# RX8E.net
KiCad netlist of a schematic drawn in EAGLE
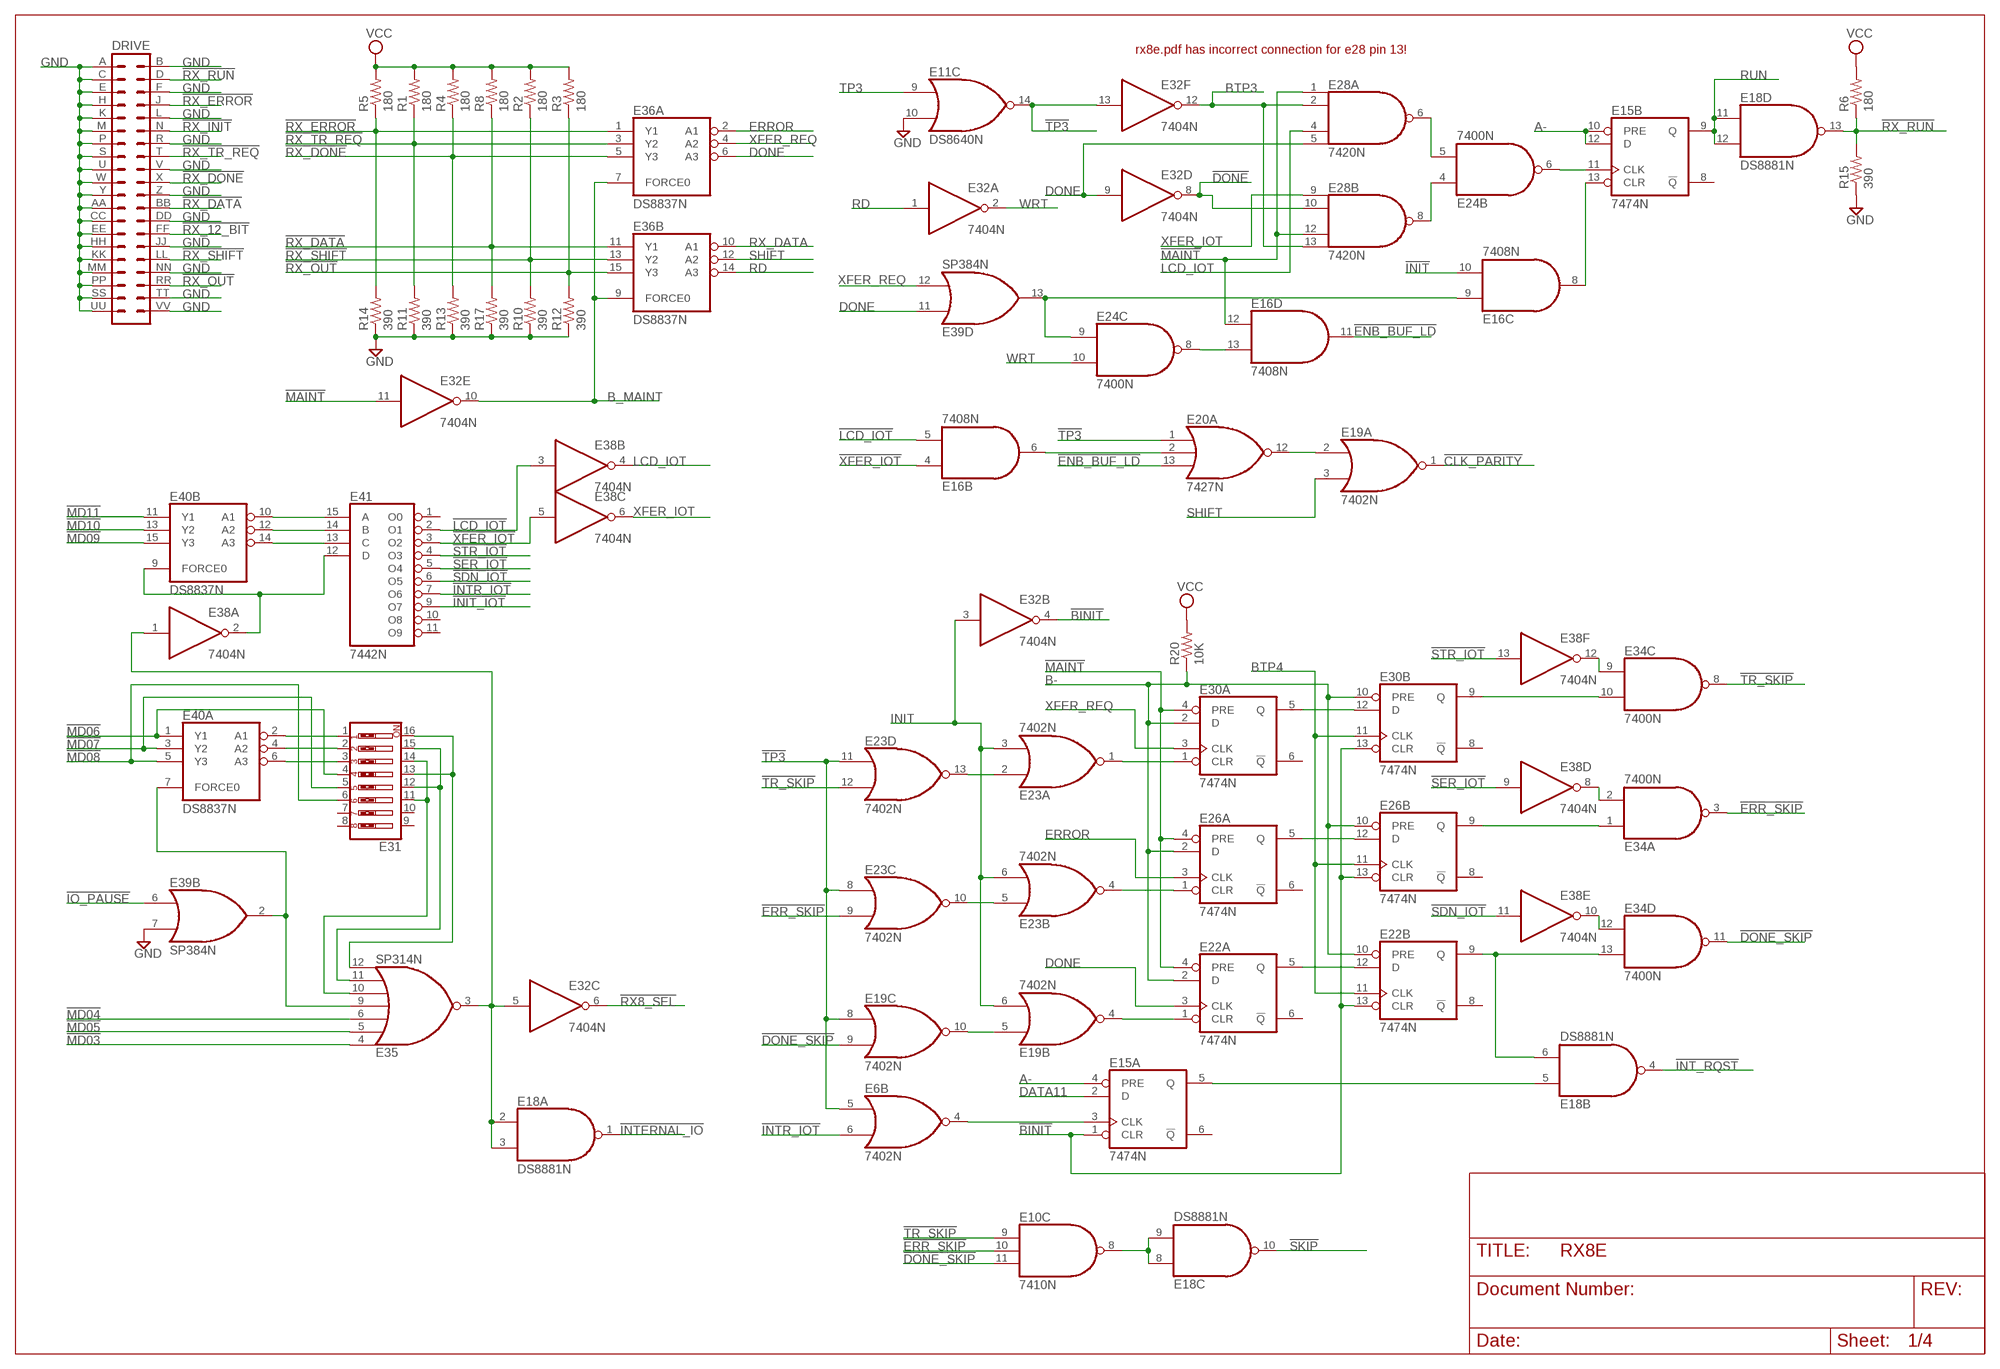
[diagram p0: schematic, sheet 1]
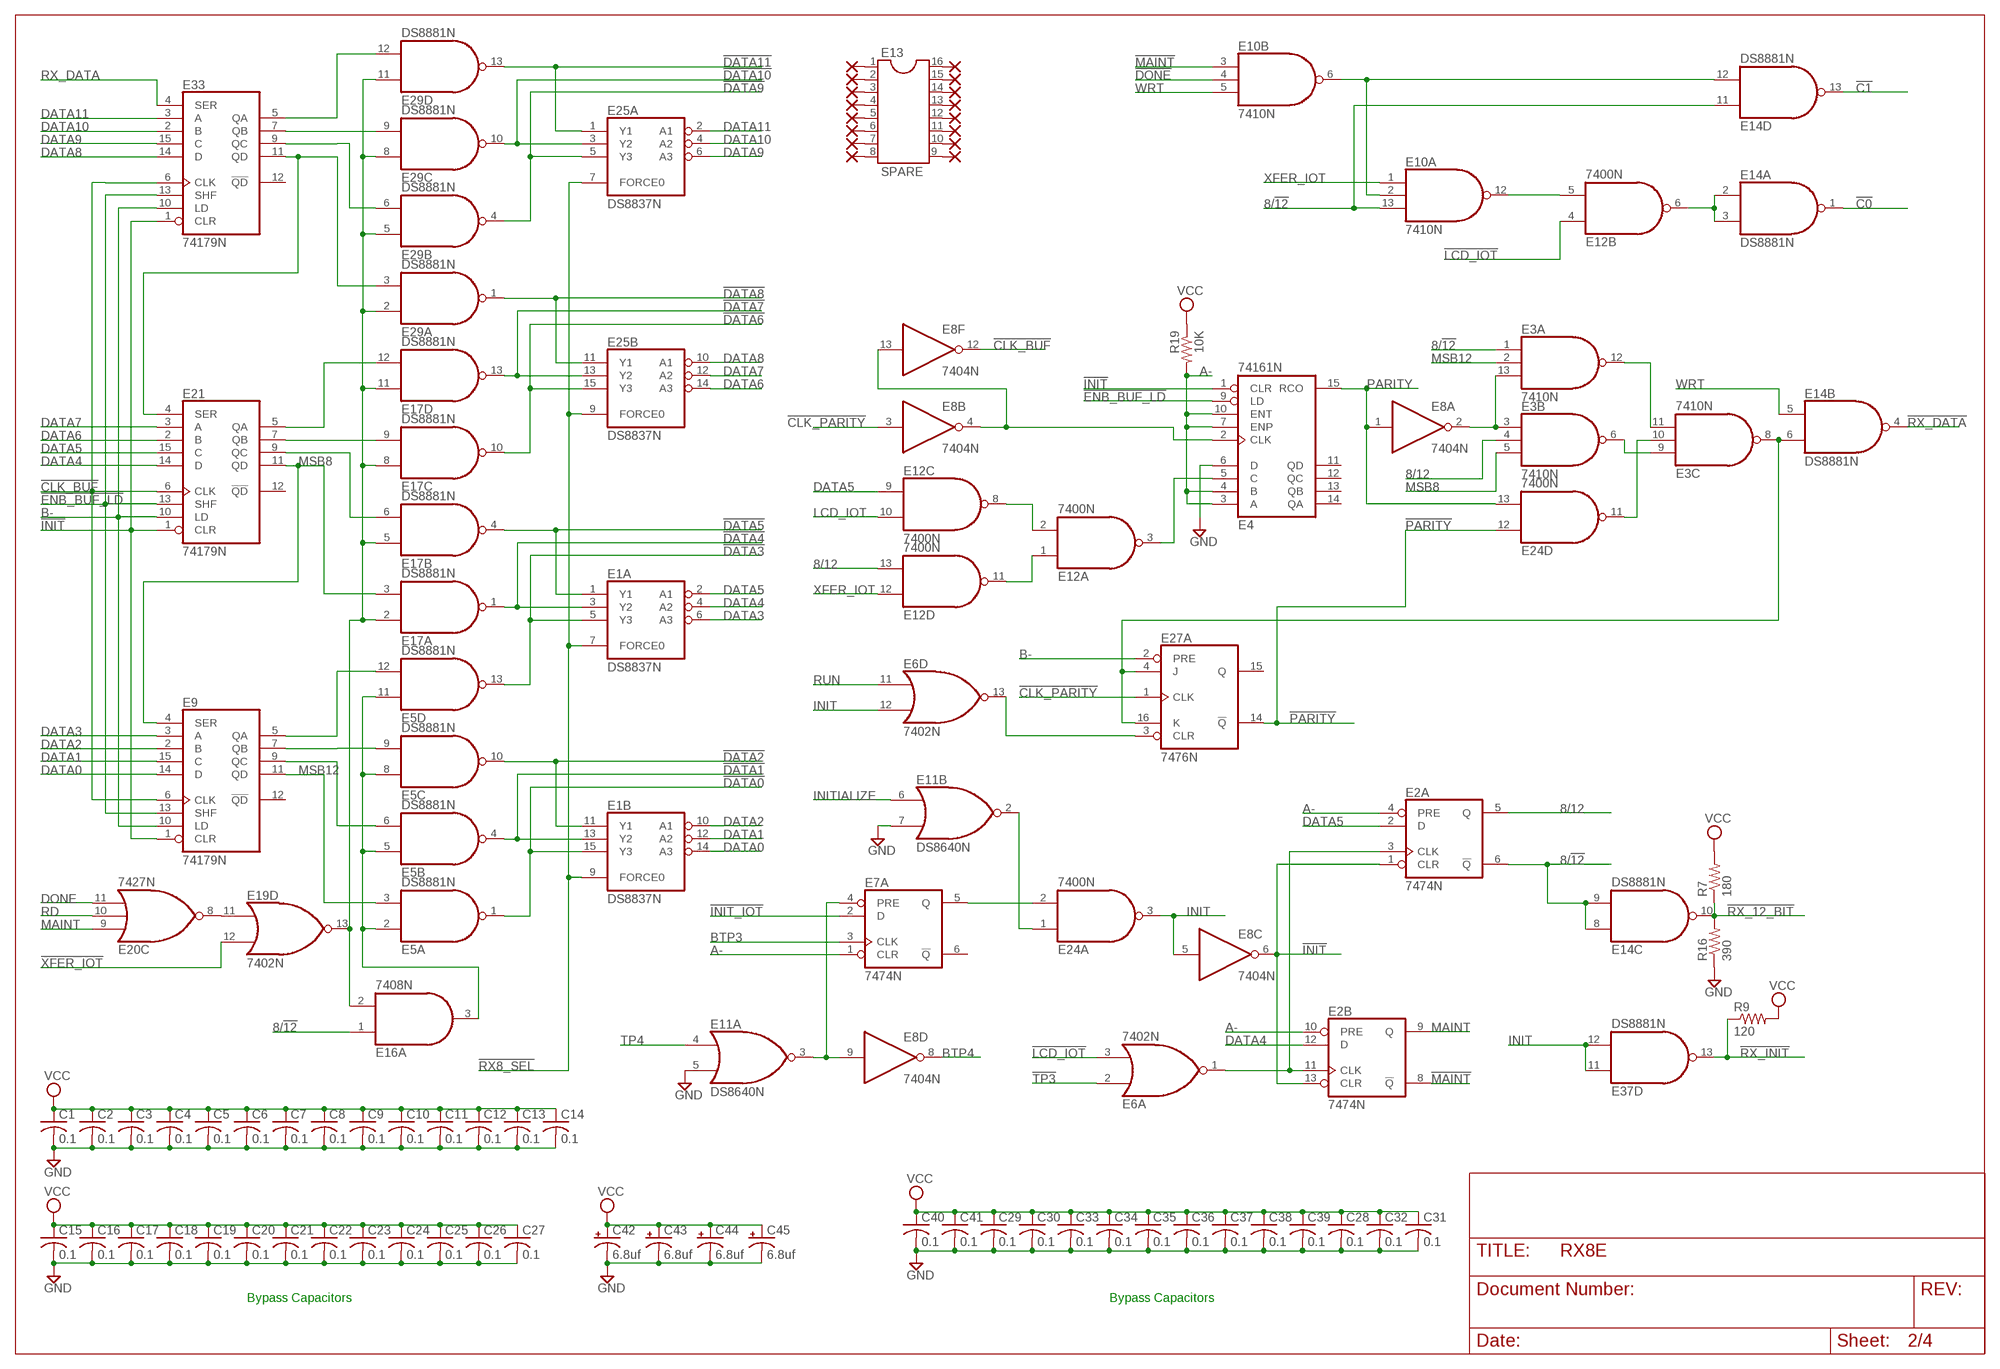
[diagram p1: schematic, sheet 2]
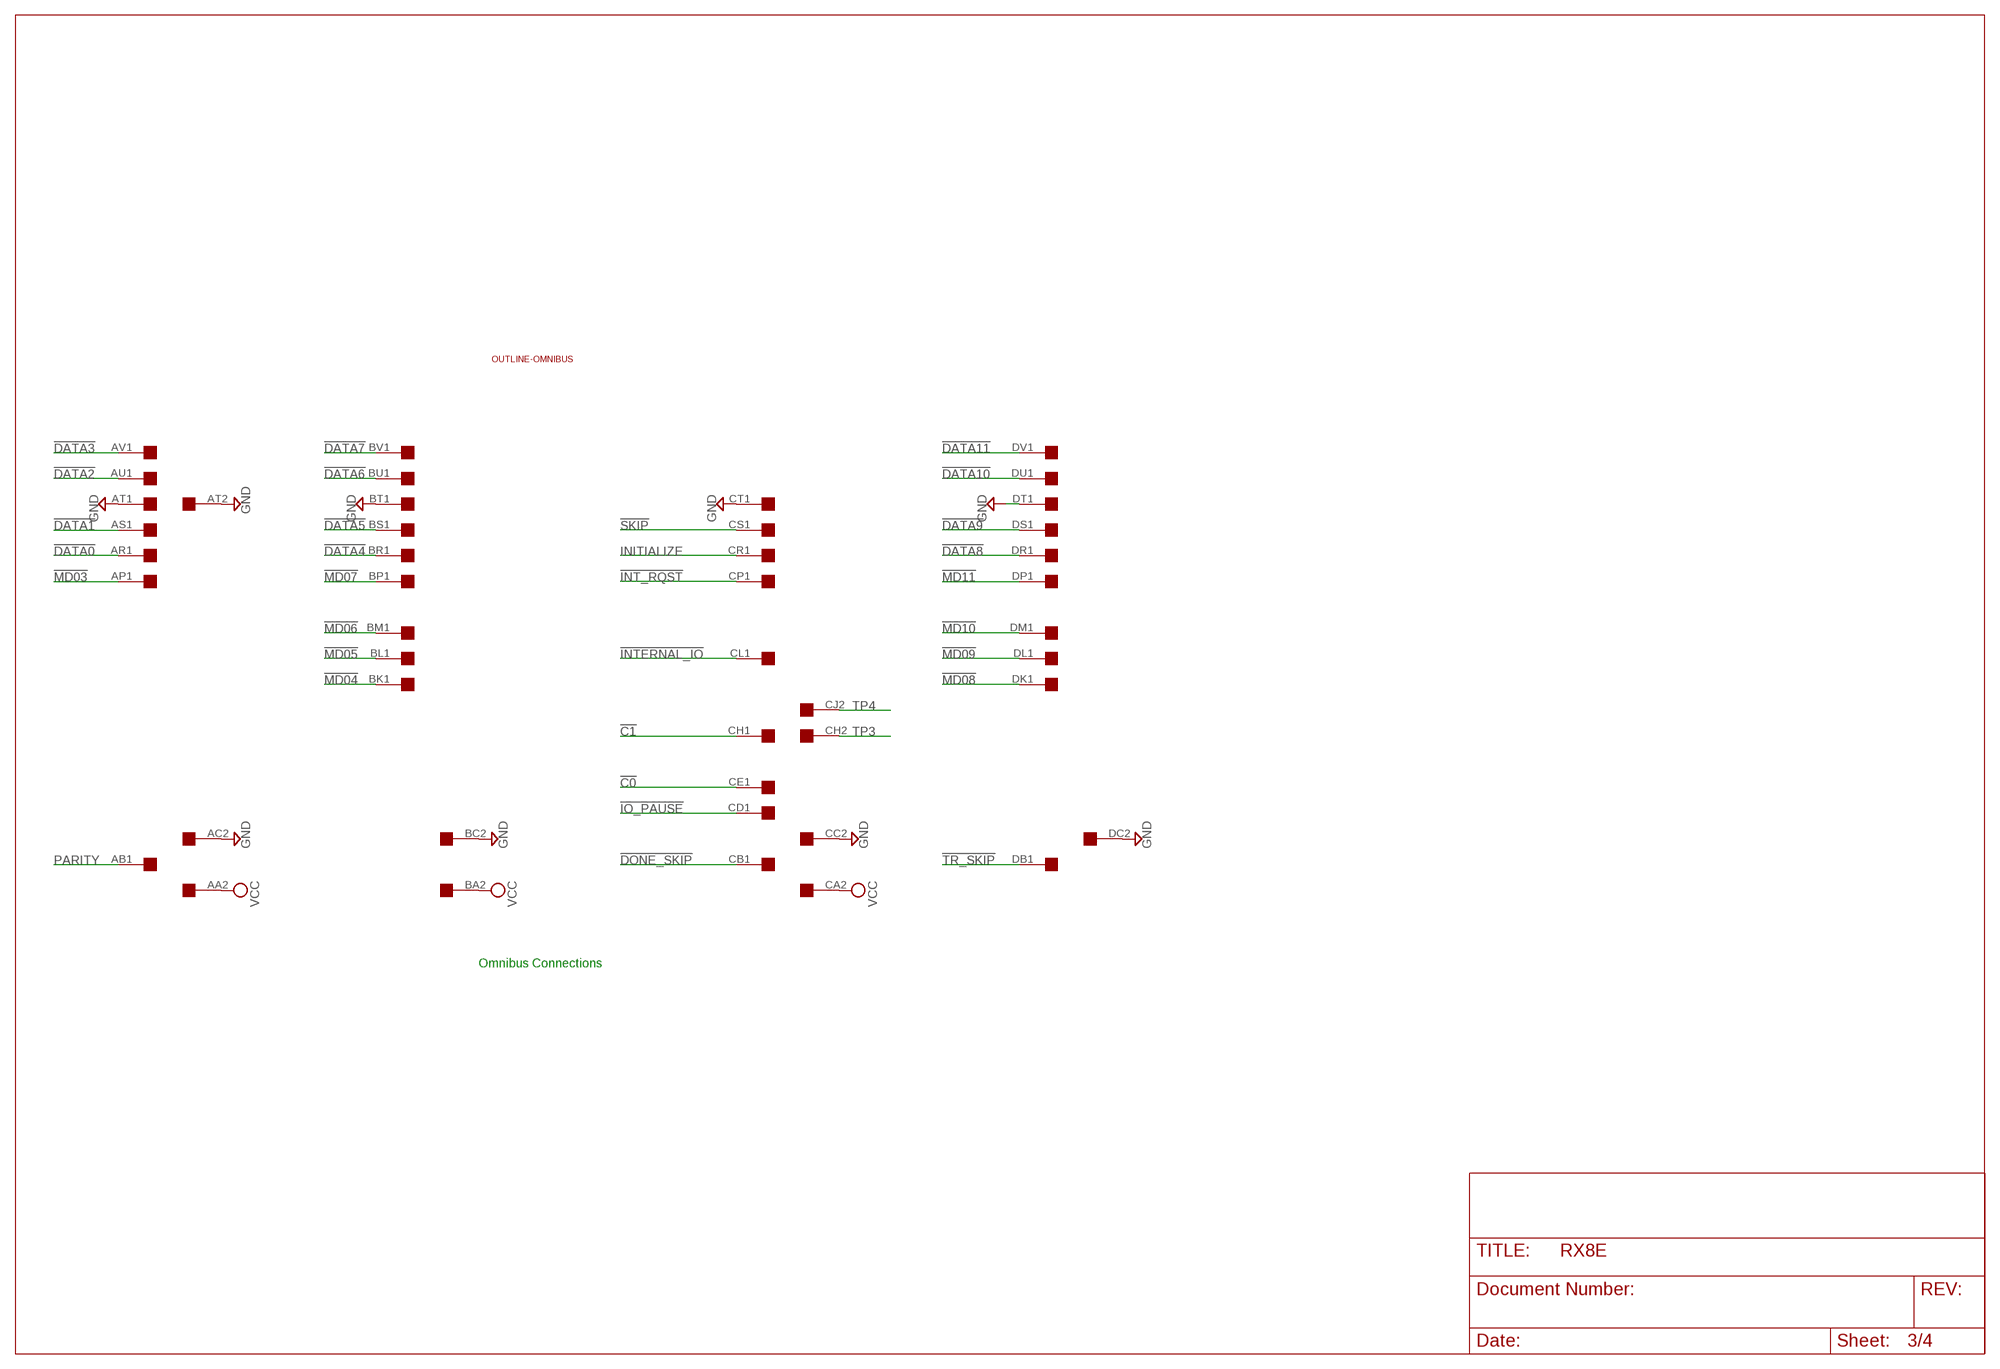
[diagram p2: schematic, sheet 3]
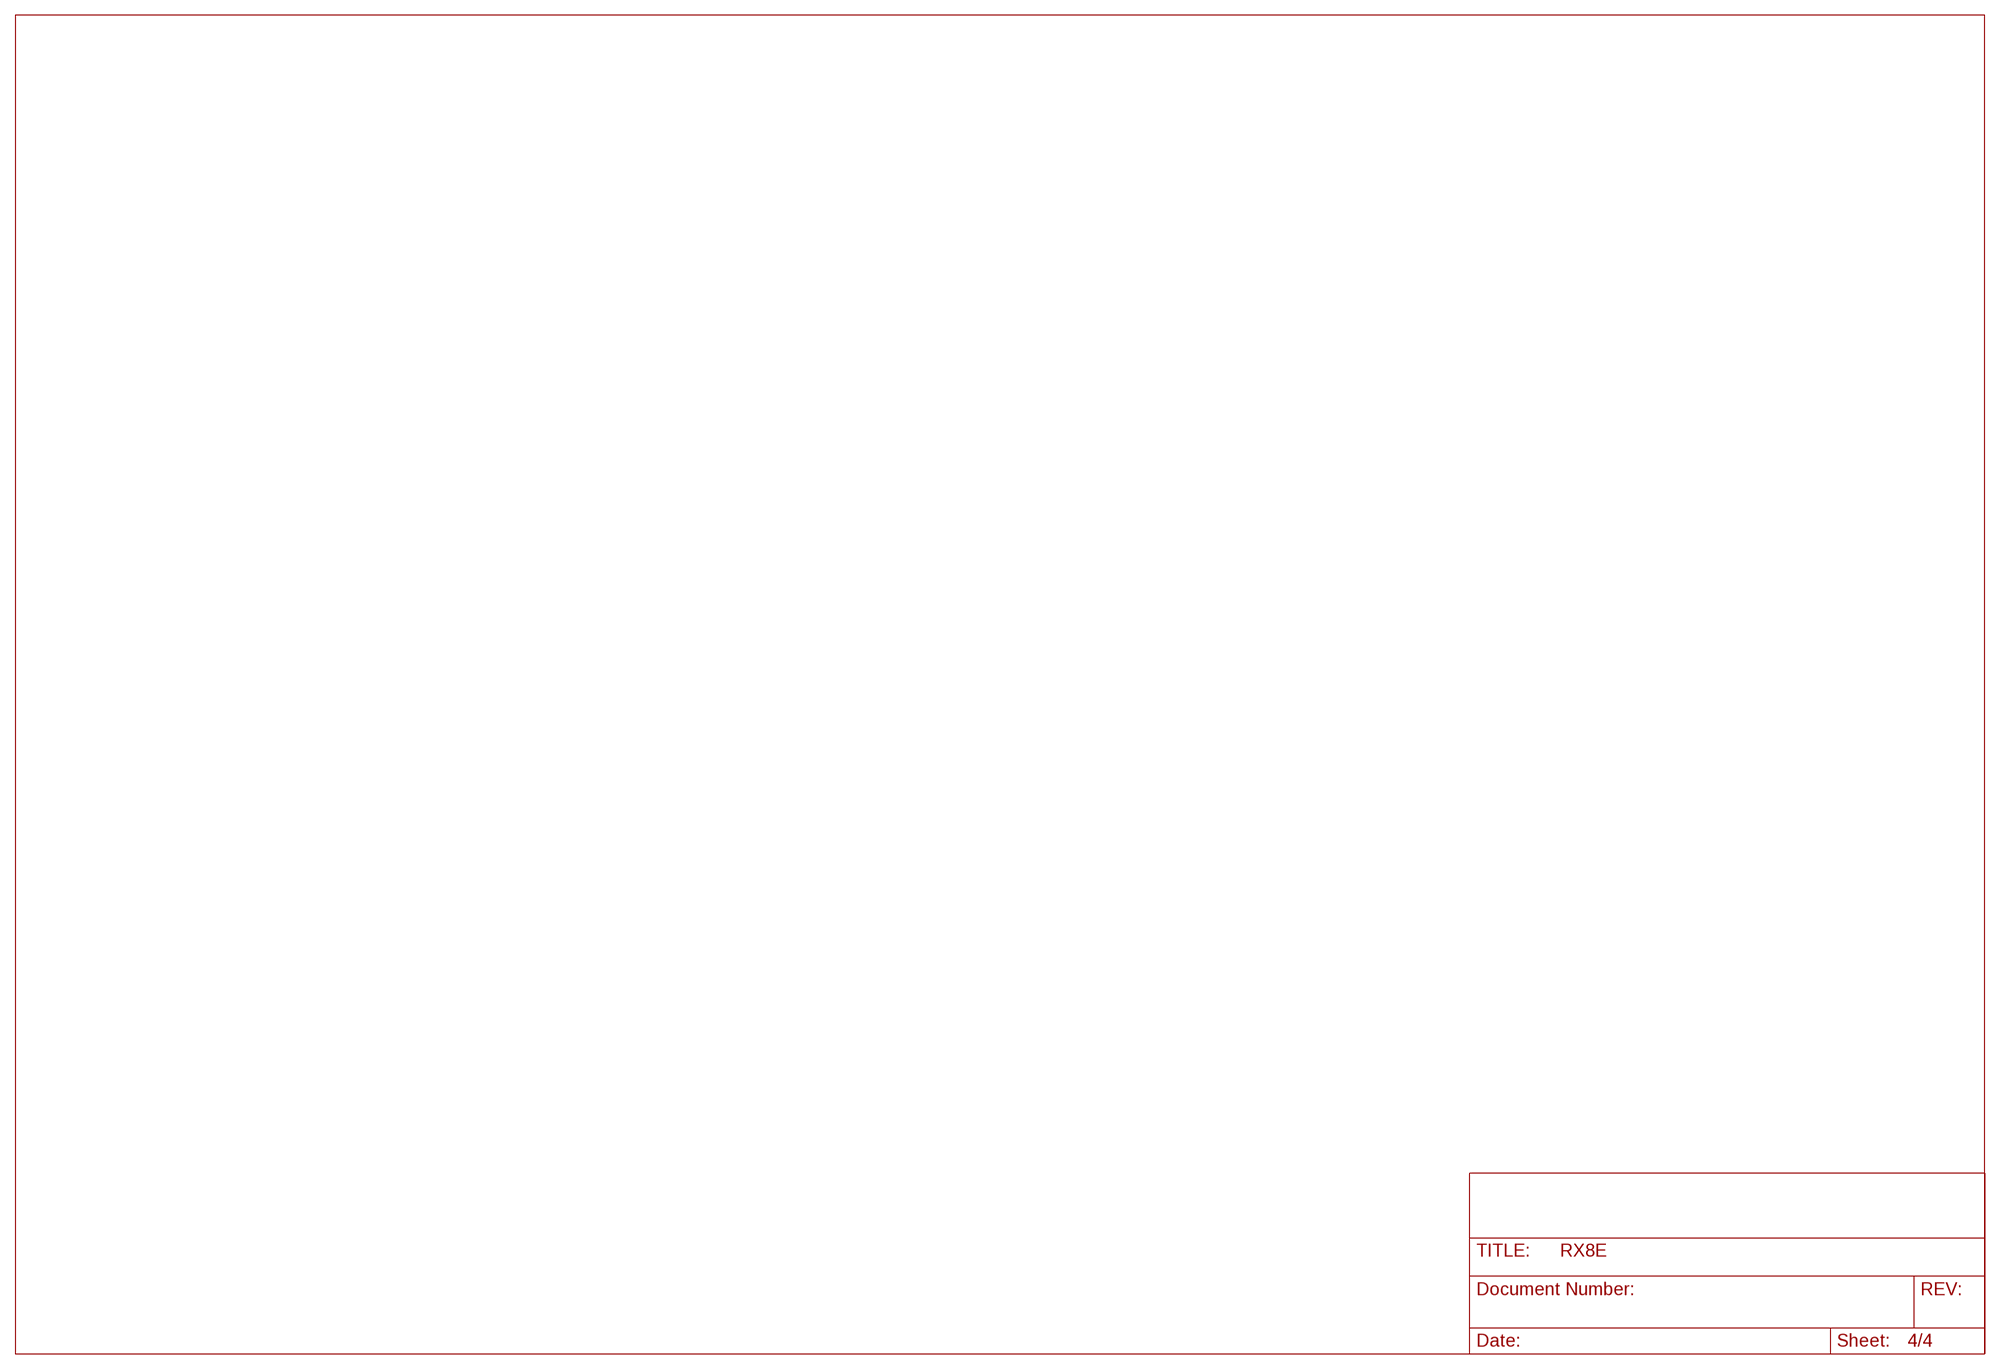
[diagram p3: schematic, sheet 4]

(export (version "E")
  (design (tool "Eeschema 10.0.6"))
  (components
    (comp (ref "U$2")
      (value "QUAD")
      (footprint "eagle-import:EDGE-CON8")
      (libsource (lib "eagle-import") (part "QUAD"))
    )
    (comp (ref "U$5")
      (value "OUTLINE-OMNIBUS")
      (footprint "eagle-import:OMNIBUS")
      (libsource (lib "eagle-import") (part "OUTLINE-OMNIBUS"))
    )
    (comp (ref "C1")
      (value "0.1")
      (footprint "eagle-import:C050-025X075")
      (libsource (lib "eagle-import") (part "C-US050-025X075"))
    )
    (comp (ref "C2")
      (value "0.1")
      (footprint "eagle-import:C050-025X075")
      (libsource (lib "eagle-import") (part "C-US050-025X075"))
    )
    (comp (ref "C3")
      (value "0.1")
      (footprint "eagle-import:C050-025X075")
      (libsource (lib "eagle-import") (part "C-US050-025X075"))
    )
    (comp (ref "C4")
      (value "0.1")
      (footprint "eagle-import:C050-025X075")
      (libsource (lib "eagle-import") (part "C-US050-025X075"))
    )
    (comp (ref "C5")
      (value "0.1")
      (footprint "eagle-import:C050-025X075")
      (libsource (lib "eagle-import") (part "C-US050-025X075"))
    )
    (comp (ref "C6")
      (value "0.1")
      (footprint "eagle-import:C050-025X075")
      (libsource (lib "eagle-import") (part "C-US050-025X075"))
    )
    (comp (ref "C7")
      (value "0.1")
      (footprint "eagle-import:C050-025X075")
      (libsource (lib "eagle-import") (part "C-US050-025X075"))
    )
    (comp (ref "C8")
      (value "0.1")
      (footprint "eagle-import:C050-025X075")
      (libsource (lib "eagle-import") (part "C-US050-025X075"))
    )
    (comp (ref "C9")
      (value "0.1")
      (footprint "eagle-import:C050-025X075")
      (libsource (lib "eagle-import") (part "C-US050-025X075"))
    )
    (comp (ref "C10")
      (value "0.1")
      (footprint "eagle-import:C050-025X075")
      (libsource (lib "eagle-import") (part "C-US050-025X075"))
    )
    (comp (ref "C11")
      (value "0.1")
      (footprint "eagle-import:C050-025X075")
      (libsource (lib "eagle-import") (part "C-US050-025X075"))
    )
    (comp (ref "C12")
      (value "0.1")
      (footprint "eagle-import:C050-025X075")
      (libsource (lib "eagle-import") (part "C-US050-025X075"))
    )
    (comp (ref "C13")
      (value "0.1")
      (footprint "eagle-import:C050-025X075")
      (libsource (lib "eagle-import") (part "C-US050-025X075"))
    )
    (comp (ref "C14")
      (value "0.1")
      (footprint "eagle-import:C050-025X075")
      (libsource (lib "eagle-import") (part "C-US050-025X075"))
    )
    (comp (ref "C15")
      (value "0.1")
      (footprint "eagle-import:C050-025X075")
      (libsource (lib "eagle-import") (part "C-US050-025X075"))
    )
    (comp (ref "C16")
      (value "0.1")
      (footprint "eagle-import:C050-025X075")
      (libsource (lib "eagle-import") (part "C-US050-025X075"))
    )
    (comp (ref "C17")
      (value "0.1")
      (footprint "eagle-import:C050-025X075")
      (libsource (lib "eagle-import") (part "C-US050-025X075"))
    )
    (comp (ref "C18")
      (value "0.1")
      (footprint "eagle-import:C050-025X075")
      (libsource (lib "eagle-import") (part "C-US050-025X075"))
    )
    (comp (ref "C19")
      (value "0.1")
      (footprint "eagle-import:C050-025X075")
      (libsource (lib "eagle-import") (part "C-US050-025X075"))
    )
    (comp (ref "C20")
      (value "0.1")
      (footprint "eagle-import:C050-025X075")
      (libsource (lib "eagle-import") (part "C-US050-025X075"))
    )
    (comp (ref "C21")
      (value "0.1")
      (footprint "eagle-import:C050-025X075")
      (libsource (lib "eagle-import") (part "C-US050-025X075"))
    )
    (comp (ref "C22")
      (value "0.1")
      (footprint "eagle-import:C050-025X075")
      (libsource (lib "eagle-import") (part "C-US050-025X075"))
    )
    (comp (ref "C23")
      (value "0.1")
      (footprint "eagle-import:C050-025X075")
      (libsource (lib "eagle-import") (part "C-US050-025X075"))
    )
    (comp (ref "C24")
      (value "0.1")
      (footprint "eagle-import:C050-025X075")
      (libsource (lib "eagle-import") (part "C-US050-025X075"))
    )
    (comp (ref "C25")
      (value "0.1")
      (footprint "eagle-import:C050-025X075")
      (libsource (lib "eagle-import") (part "C-US050-025X075"))
    )
    (comp (ref "C26")
      (value "0.1")
      (footprint "eagle-import:C050-025X075")
      (libsource (lib "eagle-import") (part "C-US050-025X075"))
    )
    (comp (ref "C27")
      (value "0.1")
      (footprint "eagle-import:C050-025X075")
      (libsource (lib "eagle-import") (part "C-US050-025X075"))
    )
    (comp (ref "C28")
      (value "0.1")
      (footprint "eagle-import:C050-025X075")
      (libsource (lib "eagle-import") (part "C-US050-025X075"))
    )
    (comp (ref "C29")
      (value "0.1")
      (footprint "eagle-import:C050-025X075")
      (libsource (lib "eagle-import") (part "C-US050-025X075"))
    )
    (comp (ref "C30")
      (value "0.1")
      (footprint "eagle-import:C050-025X075")
      (libsource (lib "eagle-import") (part "C-US050-025X075"))
    )
    (comp (ref "C31")
      (value "0.1")
      (footprint "eagle-import:C050-025X075")
      (libsource (lib "eagle-import") (part "C-US050-025X075"))
    )
    (comp (ref "C32")
      (value "0.1")
      (footprint "eagle-import:C050-025X075")
      (libsource (lib "eagle-import") (part "C-US050-025X075"))
    )
    (comp (ref "C33")
      (value "0.1")
      (footprint "eagle-import:C050-025X075")
      (libsource (lib "eagle-import") (part "C-US050-025X075"))
    )
    (comp (ref "C34")
      (value "0.1")
      (footprint "eagle-import:C050-025X075")
      (libsource (lib "eagle-import") (part "C-US050-025X075"))
    )
    (comp (ref "C35")
      (value "0.1")
      (footprint "eagle-import:C050-025X075")
      (libsource (lib "eagle-import") (part "C-US050-025X075"))
    )
    (comp (ref "C36")
      (value "0.1")
      (footprint "eagle-import:C050-025X075")
      (libsource (lib "eagle-import") (part "C-US050-025X075"))
    )
    (comp (ref "C37")
      (value "0.1")
      (footprint "eagle-import:C050-025X075")
      (libsource (lib "eagle-import") (part "C-US050-025X075"))
    )
    (comp (ref "C38")
      (value "0.1")
      (footprint "eagle-import:C050-025X075")
      (libsource (lib "eagle-import") (part "C-US050-025X075"))
    )
    (comp (ref "C39")
      (value "0.1")
      (footprint "eagle-import:C050-025X075")
      (libsource (lib "eagle-import") (part "C-US050-025X075"))
    )
    (comp (ref "C40")
      (value "0.1")
      (footprint "eagle-import:C050-025X075")
      (libsource (lib "eagle-import") (part "C-US050-025X075"))
    )
    (comp (ref "C41")
      (value "0.1")
      (footprint "eagle-import:C050-025X075")
      (libsource (lib "eagle-import") (part "C-US050-025X075"))
    )
    (comp (ref "C42")
      (value "6.8uf")
      (footprint "eagle-import:E22-6")
      (libsource (lib "eagle-import") (part "CPOL-USE22-6AXIAL"))
    )
    (comp (ref "C43")
      (value "6.8uf")
      (footprint "eagle-import:E22-6")
      (libsource (lib "eagle-import") (part "CPOL-USE22-6AXIAL"))
    )
    (comp (ref "C44")
      (value "6.8uf")
      (footprint "eagle-import:E22-6")
      (libsource (lib "eagle-import") (part "CPOL-USE22-6AXIAL"))
    )
    (comp (ref "C45")
      (value "6.8uf")
      (footprint "eagle-import:E22-6")
      (libsource (lib "eagle-import") (part "CPOL-USE22-6AXIAL"))
    )
    (comp (ref "E1")
      (value "DS8837N")
      (footprint "eagle-import:DIL16")
      (libsource (lib "eagle-import") (part "DS8837N"))
    )
    (comp (ref "E2")
      (value "7474N")
      (footprint "eagle-import:DIL14")
      (libsource (lib "eagle-import") (part "7474NLS"))
    )
    (comp (ref "E3")
      (value "7410N")
      (footprint "eagle-import:DIL14")
      (libsource (lib "eagle-import") (part "7410NLS"))
    )
    (comp (ref "E4")
      (value "74161N")
      (footprint "eagle-import:DIL16")
      (libsource (lib "eagle-import") (part "74161N"))
    )
    (comp (ref "E5")
      (value "DS8881N")
      (footprint "eagle-import:DIL14")
      (libsource (lib "eagle-import") (part "7401NLS"))
    )
    (comp (ref "E6")
      (value "7402N")
      (footprint "eagle-import:DIL14")
      (libsource (lib "eagle-import") (part "7402NLS"))
    )
    (comp (ref "E7")
      (value "7474N")
      (footprint "eagle-import:DIL14")
      (libsource (lib "eagle-import") (part "7474NLS"))
    )
    (comp (ref "E8")
      (value "7404N")
      (footprint "eagle-import:DIL14")
      (libsource (lib "eagle-import") (part "7404NLS"))
    )
    (comp (ref "E9")
      (value "74179N")
      (footprint "eagle-import:DIL16")
      (libsource (lib "eagle-import") (part "74179N"))
    )
    (comp (ref "E10")
      (value "7410N")
      (footprint "eagle-import:DIL14")
      (libsource (lib "eagle-import") (part "7410NLS"))
    )
    (comp (ref "E11")
      (value "DS8640N")
      (footprint "eagle-import:DIL14")
      (libsource (lib "eagle-import") (part "DS8640N"))
    )
    (comp (ref "E12")
      (value "7400N")
      (footprint "eagle-import:DIL14")
      (libsource (lib "eagle-import") (part "7400NLS"))
    )
    (comp (ref "E13")
      (value "SPARE")
      (footprint "eagle-import:DIL16")
      (libsource (lib "eagle-import") (part "DIL16"))
    )
    (comp (ref "E14")
      (value "DS8881N")
      (footprint "eagle-import:DIL14")
      (libsource (lib "eagle-import") (part "7401NLS"))
    )
    (comp (ref "E16")
      (value "7408N")
      (footprint "eagle-import:DIL14")
      (libsource (lib "eagle-import") (part "7408NLS"))
    )
    (comp (ref "E17")
      (value "DS8881N")
      (footprint "eagle-import:DIL14")
      (libsource (lib "eagle-import") (part "7401NLS"))
    )
    (comp (ref "E19")
      (value "7402N")
      (footprint "eagle-import:DIL14")
      (libsource (lib "eagle-import") (part "7402NLS"))
    )
    (comp (ref "E20")
      (value "7427N")
      (footprint "eagle-import:DIL14")
      (libsource (lib "eagle-import") (part "7427NLS"))
    )
    (comp (ref "E21")
      (value "74179N")
      (footprint "eagle-import:DIL16")
      (libsource (lib "eagle-import") (part "74179N"))
    )
    (comp (ref "E24")
      (value "7400N")
      (footprint "eagle-import:DIL14")
      (libsource (lib "eagle-import") (part "7400NLS"))
    )
    (comp (ref "E25")
      (value "DS8837N")
      (footprint "eagle-import:DIL16")
      (libsource (lib "eagle-import") (part "DS8837N"))
    )
    (comp (ref "E27")
      (value "7476N")
      (footprint "eagle-import:DIL16")
      (libsource (lib "eagle-import") (part "7476N"))
    )
    (comp (ref "E29")
      (value "DS8881N")
      (footprint "eagle-import:DIL14")
      (libsource (lib "eagle-import") (part "7401NLS"))
    )
    (comp (ref "E33")
      (value "74179N")
      (footprint "eagle-import:DIL16")
      (libsource (lib "eagle-import") (part "74179N"))
    )
    (comp (ref "E37")
      (value "DS8881N")
      (footprint "eagle-import:DIL14")
      (libsource (lib "eagle-import") (part "7401NLS"))
    )
    (comp (ref "PAD10")
      (value "1,6/0,8")
      (footprint "eagle-import:1,6_0,8")
      (libsource (lib "eagle-import") (part "1,6/0,8"))
    )
    (comp (ref "PAD11")
      (value "1,6/0,8")
      (footprint "eagle-import:1,6_0,8")
      (libsource (lib "eagle-import") (part "1,6/0,8"))
    )
    (comp (ref "PAD12")
      (value "1,6/0,8")
      (footprint "eagle-import:1,6_0,8")
      (libsource (lib "eagle-import") (part "1,6/0,8"))
    )
    (comp (ref "PAD13")
      (value "1,6/0,8")
      (footprint "eagle-import:1,6_0,8")
      (libsource (lib "eagle-import") (part "1,6/0,8"))
    )
    (comp (ref "PAD14")
      (value "1,6/0,8")
      (footprint "eagle-import:1,6_0,8")
      (libsource (lib "eagle-import") (part "1,6/0,8"))
    )
    (comp (ref "PAD15")
      (value "1,6/0,8")
      (footprint "eagle-import:1,6_0,8")
      (libsource (lib "eagle-import") (part "1,6/0,8"))
    )
    (comp (ref "PAD16")
      (value "1,6/0,8")
      (footprint "eagle-import:1,6_0,8")
      (libsource (lib "eagle-import") (part "1,6/0,8"))
    )
    (comp (ref "PAD17")
      (value "1,6/0,8")
      (footprint "eagle-import:1,6_0,8")
      (libsource (lib "eagle-import") (part "1,6/0,8"))
    )
    (comp (ref "PAD20")
      (value "1,6/0,8")
      (footprint "eagle-import:1,6_0,8")
      (libsource (lib "eagle-import") (part "1,6/0,8"))
    )
    (comp (ref "PAD21")
      (value "1,6/0,8")
      (footprint "eagle-import:1,6_0,8")
      (libsource (lib "eagle-import") (part "1,6/0,8"))
    )
    (comp (ref "PAD22")
      (value "1,6/0,8")
      (footprint "eagle-import:1,6_0,8")
      (libsource (lib "eagle-import") (part "1,6/0,8"))
    )
    (comp (ref "PAD23")
      (value "1,6/0,8")
      (footprint "eagle-import:1,6_0,8")
      (libsource (lib "eagle-import") (part "1,6/0,8"))
    )
    (comp (ref "PAD24")
      (value "1,6/0,8")
      (footprint "eagle-import:1,6_0,8")
      (libsource (lib "eagle-import") (part "1,6/0,8"))
    )
    (comp (ref "PAD25")
      (value "1,6/0,8")
      (footprint "eagle-import:1,6_0,8")
      (libsource (lib "eagle-import") (part "1,6/0,8"))
    )
    (comp (ref "PAD26")
      (value "1,6/0,8")
      (footprint "eagle-import:1,6_0,8")
      (libsource (lib "eagle-import") (part "1,6/0,8"))
    )
    (comp (ref "PAD27")
      (value "1,6/0,8")
      (footprint "eagle-import:1,6_0,8")
      (libsource (lib "eagle-import") (part "1,6/0,8"))
    )
    (comp (ref "R7")
      (value "180")
      (footprint "eagle-import:0207_10")
      (libsource (lib "eagle-import") (part "R-US_0207/10"))
    )
    (comp (ref "R9")
      (value "120")
      (footprint "eagle-import:0207_10")
      (libsource (lib "eagle-import") (part "R-US_0207/10"))
    )
    (comp (ref "R16")
      (value "390")
      (footprint "eagle-import:0207_10")
      (libsource (lib "eagle-import") (part "R-US_0207/10"))
    )
    (comp (ref "R19")
      (value "10K")
      (footprint "eagle-import:0207_10")
      (libsource (lib "eagle-import") (part "R-US_0207/10"))
    )
    (comp (ref "DRIVE")
      (value "DEC40PINH")
      (footprint "eagle-import:DEC40PINH")
      (libsource (lib "eagle-import") (part "DEC40PINH"))
    )
    (comp (ref "E15")
      (value "7474N")
      (footprint "eagle-import:DIL14")
      (libsource (lib "eagle-import") (part "7474NLS"))
    )
    (comp (ref "E18")
      (value "DS8881N")
      (footprint "eagle-import:DIL14")
      (libsource (lib "eagle-import") (part "7401NLS"))
    )
    (comp (ref "E22")
      (value "7474N")
      (footprint "eagle-import:DIL14")
      (libsource (lib "eagle-import") (part "7474NLS"))
    )
    (comp (ref "E23")
      (value "7402N")
      (footprint "eagle-import:DIL14")
      (libsource (lib "eagle-import") (part "7402NLS"))
    )
    (comp (ref "E26")
      (value "7474N")
      (footprint "eagle-import:DIL14")
      (libsource (lib "eagle-import") (part "7474NLS"))
    )
    (comp (ref "E28")
      (value "7420N")
      (footprint "eagle-import:DIL14")
      (libsource (lib "eagle-import") (part "7420NLS"))
    )
    (comp (ref "E30")
      (value "7474N")
      (footprint "eagle-import:DIL14")
      (libsource (lib "eagle-import") (part "7474NLS"))
    )
    (comp (ref "E31")
      (value "SW_DIP-8")
      (footprint "eagle-import:EDG-08")
      (libsource (lib "eagle-import") (part "SW_DIP-8"))
    )
    (comp (ref "E32")
      (value "7404N")
      (footprint "eagle-import:DIL14")
      (libsource (lib "eagle-import") (part "7404NLS"))
    )
    (comp (ref "E34")
      (value "7400N")
      (footprint "eagle-import:DIL14")
      (libsource (lib "eagle-import") (part "7400N"))
    )
    (comp (ref "E35")
      (value "SP314N")
      (footprint "eagle-import:DIL14")
      (libsource (lib "eagle-import") (part "SP314N"))
    )
    (comp (ref "E36")
      (value "DS8837N")
      (footprint "eagle-import:DIL16")
      (libsource (lib "eagle-import") (part "DS8837N"))
    )
    (comp (ref "E38")
      (value "7404N")
      (footprint "eagle-import:DIL14")
      (libsource (lib "eagle-import") (part "7404NLS"))
    )
    (comp (ref "E39")
      (value "SP384N")
      (footprint "eagle-import:DIL14")
      (libsource (lib "eagle-import") (part "SP384N"))
    )
    (comp (ref "E40")
      (value "DS8837N")
      (footprint "eagle-import:DIL16")
      (libsource (lib "eagle-import") (part "DS8837N"))
    )
    (comp (ref "E41")
      (value "7442N")
      (footprint "eagle-import:DIL16")
      (libsource (lib "eagle-import") (part "7442NLS"))
    )
    (comp (ref "R1")
      (value "180")
      (footprint "eagle-import:0207_10")
      (libsource (lib "eagle-import") (part "R-US_0207/10"))
    )
    (comp (ref "R2")
      (value "180")
      (footprint "eagle-import:0207_10")
      (libsource (lib "eagle-import") (part "R-US_0207/10"))
    )
    (comp (ref "R3")
      (value "180")
      (footprint "eagle-import:0207_10")
      (libsource (lib "eagle-import") (part "R-US_0207/10"))
    )
    (comp (ref "R4")
      (value "180")
      (footprint "eagle-import:0207_10")
      (libsource (lib "eagle-import") (part "R-US_0207/10"))
    )
    (comp (ref "R5")
      (value "180")
      (footprint "eagle-import:0207_10")
      (libsource (lib "eagle-import") (part "R-US_0207/10"))
    )
    (comp (ref "R6")
      (value "180")
      (footprint "eagle-import:0207_10")
      (libsource (lib "eagle-import") (part "R-US_0207/10"))
    )
    (comp (ref "R8")
      (value "180")
      (footprint "eagle-import:0207_10")
      (libsource (lib "eagle-import") (part "R-US_0207/10"))
    )
    (comp (ref "R10")
      (value "390")
      (footprint "eagle-import:0207_10")
      (libsource (lib "eagle-import") (part "R-US_0207/10"))
    )
    (comp (ref "R11")
      (value "390")
      (footprint "eagle-import:0207_10")
      (libsource (lib "eagle-import") (part "R-US_0207/10"))
    )
    (comp (ref "R12")
      (value "390")
      (footprint "eagle-import:0207_10")
      (libsource (lib "eagle-import") (part "R-US_0207/10"))
    )
    (comp (ref "R13")
      (value "390")
      (footprint "eagle-import:0207_10")
      (libsource (lib "eagle-import") (part "R-US_0207/10"))
    )
    (comp (ref "R14")
      (value "390")
      (footprint "eagle-import:0207_10")
      (libsource (lib "eagle-import") (part "R-US_0207/10"))
    )
    (comp (ref "R15")
      (value "390")
      (footprint "eagle-import:0207_10")
      (libsource (lib "eagle-import") (part "R-US_0207/10"))
    )
    (comp (ref "R17")
      (value "390")
      (footprint "eagle-import:0207_10")
      (libsource (lib "eagle-import") (part "R-US_0207/10"))
    )
    (comp (ref "R20")
      (value "10K")
      (footprint "eagle-import:0207_10")
      (libsource (lib "eagle-import") (part "R-US_0207/10"))
    )
  )
  (nets
    (net (code "1") (name "8{slash}12") (class "Default")
      (node (ref "E12") (pin "13") (pinfunction "I1_13") (pintype "input"))
      (node (ref "E2") (pin "5") (pinfunction "Q_5") (pintype "output"))
      (node (ref "E3") (pin "4") (pinfunction "I1_4") (pintype "input"))
    )
    (net (code "2") (name "8{slash}~{12}") (class "Default")
      (node (ref "E10") (pin "13") (pinfunction "I2_13") (pintype "input"))
      (node (ref "E14") (pin "11") (pinfunction "I0_11") (pintype "input"))
      (node (ref "E14") (pin "8") (pinfunction "I0_8") (pintype "input"))
      (node (ref "E14") (pin "9") (pinfunction "I1_9") (pintype "input"))
      (node (ref "E16") (pin "1") (pinfunction "I0_1") (pintype "input"))
      (node (ref "E2") (pin "6") (pinfunction "~{Q}_6") (pintype "output"))
      (node (ref "E3") (pin "1") (pinfunction "I0_1") (pintype "input"))
    )
    (net (code "3") (name "A-") (class "Default")
      (node (ref "E15") (pin "10") (pinfunction "PRE_10") (pintype "input"))
      (node (ref "E15") (pin "12") (pinfunction "D_12") (pintype "input"))
      (node (ref "E15") (pin "4") (pinfunction "PRE_4") (pintype "input"))
      (node (ref "E2") (pin "10") (pinfunction "PRE_10") (pintype "input"))
      (node (ref "E2") (pin "4") (pinfunction "PRE_4") (pintype "input"))
      (node (ref "E4") (pin "10") (pinfunction "ENT_10") (pintype "input"))
      (node (ref "E4") (pin "3") (pinfunction "A_3") (pintype "input"))
      (node (ref "E4") (pin "4") (pinfunction "B_4") (pintype "input"))
      (node (ref "E4") (pin "7") (pinfunction "ENP_7") (pintype "input"))
      (node (ref "E7") (pin "1") (pinfunction "CLR_1") (pintype "input"))
      (node (ref "R19") (pin "2") (pinfunction "2_2") (pintype "passive"))
    )
    (net (code "4") (name "B-") (class "Default")
      (node (ref "E21") (pin "10") (pinfunction "LD_10") (pintype "input"))
      (node (ref "E22") (pin "10") (pinfunction "PRE_10") (pintype "input"))
      (node (ref "E22") (pin "2") (pinfunction "D_2") (pintype "input"))
      (node (ref "E26") (pin "10") (pinfunction "PRE_10") (pintype "input"))
      (node (ref "E26") (pin "2") (pinfunction "D_2") (pintype "input"))
      (node (ref "E27") (pin "2") (pinfunction "PRE_2") (pintype "input"))
      (node (ref "E30") (pin "10") (pinfunction "PRE_10") (pintype "input"))
      (node (ref "E30") (pin "2") (pinfunction "D_2") (pintype "input"))
      (node (ref "E33") (pin "10") (pinfunction "LD_10") (pintype "input"))
      (node (ref "E9") (pin "10") (pinfunction "LD_10") (pintype "input"))
      (node (ref "R20") (pin "1") (pinfunction "1_1") (pintype "passive"))
    )
    (net (code "5") (name "BTP3") (class "Default")
      (node (ref "E28") (pin "13") (pinfunction "I3_13") (pintype "input"))
      (node (ref "E28") (pin "2") (pinfunction "I1_2") (pintype "input"))
      (node (ref "E32") (pin "12") (pinfunction "O_12") (pintype "output"))
      (node (ref "E7") (pin "3") (pinfunction "CLK_3") (pintype "input"))
    )
    (net (code "6") (name "BTP4") (class "Default")
      (node (ref "E22") (pin "11") (pinfunction "CLK_11") (pintype "input"))
      (node (ref "E26") (pin "11") (pinfunction "CLK_11") (pintype "input"))
      (node (ref "E30") (pin "11") (pinfunction "CLK_11") (pintype "input"))
      (node (ref "E8") (pin "8") (pinfunction "O_8") (pintype "output"))
    )
    (net (code "7") (name "B_MAINT") (class "Default")
      (node (ref "E32") (pin "10") (pinfunction "O_10") (pintype "output"))
      (node (ref "E36") (pin "7") (pinfunction "FORCE0_7") (pintype "input"))
      (node (ref "E36") (pin "9") (pinfunction "FORCE0_9") (pintype "input"))
    )
    (net (code "8") (name "DATA0") (class "Default")
      (node (ref "E1") (pin "14") (pinfunction "A3_14") (pintype "output"))
      (node (ref "E9") (pin "14") (pinfunction "D_14") (pintype "input"))
    )
    (net (code "9") (name "DATA1") (class "Default")
      (node (ref "E1") (pin "12") (pinfunction "A2_12") (pintype "output"))
      (node (ref "E9") (pin "15") (pinfunction "C_15") (pintype "input"))
    )
    (net (code "10") (name "DATA2") (class "Default")
      (node (ref "E1") (pin "10") (pinfunction "A1_10") (pintype "output"))
      (node (ref "E9") (pin "2") (pinfunction "B_2") (pintype "input"))
    )
    (net (code "11") (name "DATA3") (class "Default")
      (node (ref "E1") (pin "6") (pinfunction "A3_6") (pintype "output"))
      (node (ref "E9") (pin "3") (pinfunction "A_3") (pintype "input"))
    )
    (net (code "12") (name "DATA4") (class "Default")
      (node (ref "E1") (pin "4") (pinfunction "A2_4") (pintype "output"))
      (node (ref "E2") (pin "12") (pinfunction "D_12") (pintype "input"))
      (node (ref "E21") (pin "14") (pinfunction "D_14") (pintype "input"))
    )
    (net (code "13") (name "DATA5") (class "Default")
      (node (ref "E1") (pin "2") (pinfunction "A1_2") (pintype "output"))
      (node (ref "E12") (pin "9") (pinfunction "I0_9") (pintype "input"))
      (node (ref "E2") (pin "2") (pinfunction "D_2") (pintype "input"))
      (node (ref "E21") (pin "15") (pinfunction "C_15") (pintype "input"))
    )
    (net (code "14") (name "DATA6") (class "Default")
      (node (ref "E21") (pin "2") (pinfunction "B_2") (pintype "input"))
      (node (ref "E25") (pin "14") (pinfunction "A3_14") (pintype "output"))
    )
    (net (code "15") (name "DATA7") (class "Default")
      (node (ref "E21") (pin "3") (pinfunction "A_3") (pintype "input"))
      (node (ref "E25") (pin "12") (pinfunction "A2_12") (pintype "output"))
    )
    (net (code "16") (name "DATA8") (class "Default")
      (node (ref "E25") (pin "10") (pinfunction "A1_10") (pintype "output"))
      (node (ref "E33") (pin "14") (pinfunction "D_14") (pintype "input"))
    )
    (net (code "17") (name "DATA9") (class "Default")
      (node (ref "E25") (pin "6") (pinfunction "A3_6") (pintype "output"))
      (node (ref "E33") (pin "15") (pinfunction "C_15") (pintype "input"))
    )
    (net (code "18") (name "DATA10") (class "Default")
      (node (ref "E25") (pin "4") (pinfunction "A2_4") (pintype "output"))
      (node (ref "E33") (pin "2") (pinfunction "B_2") (pintype "input"))
    )
    (net (code "19") (name "DATA11") (class "Default")
      (node (ref "E15") (pin "2") (pinfunction "D_2") (pintype "input"))
      (node (ref "E25") (pin "2") (pinfunction "A1_2") (pintype "output"))
      (node (ref "E33") (pin "3") (pinfunction "A_3") (pintype "input"))
    )
    (net (code "20") (name "DONE") (class "Default")
      (node (ref "E20") (pin "11") (pinfunction "I2_11") (pintype "input"))
      (node (ref "E22") (pin "3") (pinfunction "CLK_3") (pintype "input"))
      (node (ref "E28") (pin "5") (pinfunction "I3_5") (pintype "input"))
      (node (ref "E32") (pin "9") (pinfunction "I_9") (pintype "input"))
      (node (ref "E36") (pin "6") (pinfunction "A3_6") (pintype "output"))
      (node (ref "E39") (pin "11") (pinfunction "I0_11") (pintype "input"))
    )
    (net (code "21") (name "ERROR") (class "Default")
      (node (ref "E26") (pin "3") (pinfunction "CLK_3") (pintype "input"))
      (node (ref "E36") (pin "2") (pinfunction "A1_2") (pintype "output"))
    )
    (net (code "22") (name "GND") (class "Default")
      (node (ref "C1") (pin "2") (pinfunction "2_2") (pintype "passive"))
      (node (ref "C10") (pin "2") (pinfunction "2_2") (pintype "passive"))
      (node (ref "C11") (pin "2") (pinfunction "2_2") (pintype "passive"))
      (node (ref "C12") (pin "2") (pinfunction "2_2") (pintype "passive"))
      (node (ref "C13") (pin "2") (pinfunction "2_2") (pintype "passive"))
      (node (ref "C14") (pin "2") (pinfunction "2_2") (pintype "passive"))
      (node (ref "C15") (pin "2") (pinfunction "2_2") (pintype "passive"))
      (node (ref "C16") (pin "2") (pinfunction "2_2") (pintype "passive"))
      (node (ref "C17") (pin "2") (pinfunction "2_2") (pintype "passive"))
      (node (ref "C18") (pin "2") (pinfunction "2_2") (pintype "passive"))
      (node (ref "C19") (pin "2") (pinfunction "2_2") (pintype "passive"))
      (node (ref "C2") (pin "2") (pinfunction "2_2") (pintype "passive"))
      (node (ref "C20") (pin "2") (pinfunction "2_2") (pintype "passive"))
      (node (ref "C21") (pin "2") (pinfunction "2_2") (pintype "passive"))
      (node (ref "C22") (pin "2") (pinfunction "2_2") (pintype "passive"))
      (node (ref "C23") (pin "2") (pinfunction "2_2") (pintype "passive"))
      (node (ref "C24") (pin "2") (pinfunction "2_2") (pintype "passive"))
      (node (ref "C25") (pin "2") (pinfunction "2_2") (pintype "passive"))
      (node (ref "C26") (pin "2") (pinfunction "2_2") (pintype "passive"))
      (node (ref "C27") (pin "2") (pinfunction "2_2") (pintype "passive"))
      (node (ref "C28") (pin "2") (pinfunction "2_2") (pintype "passive"))
      (node (ref "C29") (pin "2") (pinfunction "2_2") (pintype "passive"))
      (node (ref "C3") (pin "2") (pinfunction "2_2") (pintype "passive"))
      (node (ref "C30") (pin "2") (pinfunction "2_2") (pintype "passive"))
      (node (ref "C31") (pin "2") (pinfunction "2_2") (pintype "passive"))
      (node (ref "C32") (pin "2") (pinfunction "2_2") (pintype "passive"))
      (node (ref "C33") (pin "2") (pinfunction "2_2") (pintype "passive"))
      (node (ref "C34") (pin "2") (pinfunction "2_2") (pintype "passive"))
      (node (ref "C35") (pin "2") (pinfunction "2_2") (pintype "passive"))
      (node (ref "C36") (pin "2") (pinfunction "2_2") (pintype "passive"))
      (node (ref "C37") (pin "2") (pinfunction "2_2") (pintype "passive"))
      (node (ref "C38") (pin "2") (pinfunction "2_2") (pintype "passive"))
      (node (ref "C39") (pin "2") (pinfunction "2_2") (pintype "passive"))
      (node (ref "C4") (pin "2") (pinfunction "2_2") (pintype "passive"))
      (node (ref "C40") (pin "2") (pinfunction "2_2") (pintype "passive"))
      (node (ref "C41") (pin "2") (pinfunction "2_2") (pintype "passive"))
      (node (ref "C42") (pin "-") (pinfunction "-_-") (pintype "passive"))
      (node (ref "C43") (pin "-") (pinfunction "-_-") (pintype "passive"))
      (node (ref "C44") (pin "-") (pinfunction "-_-") (pintype "passive"))
      (node (ref "C45") (pin "-") (pinfunction "-_-") (pintype "passive"))
      (node (ref "C5") (pin "2") (pinfunction "2_2") (pintype "passive"))
      (node (ref "C6") (pin "2") (pinfunction "2_2") (pintype "passive"))
      (node (ref "C7") (pin "2") (pinfunction "2_2") (pintype "passive"))
      (node (ref "C8") (pin "2") (pinfunction "2_2") (pintype "passive"))
      (node (ref "C9") (pin "2") (pinfunction "2_2") (pintype "passive"))
      (node (ref "DRIVE") (pin "A") (pinfunction "1_A") (pintype "bidirectional"))
      (node (ref "DRIVE") (pin "AA") (pinfunction "23_AA") (pintype "bidirectional"))
      (node (ref "DRIVE") (pin "B") (pinfunction "2_B") (pintype "bidirectional"))
      (node (ref "DRIVE") (pin "C") (pinfunction "3_C") (pintype "bidirectional"))
      (node (ref "DRIVE") (pin "CC") (pinfunction "25_CC") (pintype "bidirectional"))
      (node (ref "DRIVE") (pin "DD") (pinfunction "26_DD") (pintype "bidirectional"))
      (node (ref "DRIVE") (pin "E") (pinfunction "5_E") (pintype "bidirectional"))
      (node (ref "DRIVE") (pin "EE") (pinfunction "27_EE") (pintype "bidirectional"))
      (node (ref "DRIVE") (pin "F") (pinfunction "6_F") (pintype "bidirectional"))
      (node (ref "DRIVE") (pin "H") (pinfunction "7_H") (pintype "bidirectional"))
      (node (ref "DRIVE") (pin "HH") (pinfunction "29_HH") (pintype "bidirectional"))
      (node (ref "DRIVE") (pin "JJ") (pinfunction "30_JJ") (pintype "bidirectional"))
      (node (ref "DRIVE") (pin "K") (pinfunction "9_K") (pintype "bidirectional"))
      (node (ref "DRIVE") (pin "KK") (pinfunction "31_KK") (pintype "bidirectional"))
      (node (ref "DRIVE") (pin "L") (pinfunction "10_L") (pintype "bidirectional"))
      (node (ref "DRIVE") (pin "M") (pinfunction "11_M") (pintype "bidirectional"))
      (node (ref "DRIVE") (pin "MM") (pinfunction "33_MM") (pintype "bidirectional"))
      (node (ref "DRIVE") (pin "NN") (pinfunction "34_NN") (pintype "bidirectional"))
      (node (ref "DRIVE") (pin "P") (pinfunction "13_P") (pintype "bidirectional"))
      (node (ref "DRIVE") (pin "PP") (pinfunction "35_PP") (pintype "bidirectional"))
      (node (ref "DRIVE") (pin "R") (pinfunction "14_R") (pintype "bidirectional"))
      (node (ref "DRIVE") (pin "S") (pinfunction "15_S") (pintype "bidirectional"))
      (node (ref "DRIVE") (pin "SS") (pinfunction "37_SS") (pintype "bidirectional"))
      (node (ref "DRIVE") (pin "TT") (pinfunction "38_TT") (pintype "bidirectional"))
      (node (ref "DRIVE") (pin "U") (pinfunction "17_U") (pintype "bidirectional"))
      (node (ref "DRIVE") (pin "UU") (pinfunction "39_UU") (pintype "bidirectional"))
      (node (ref "DRIVE") (pin "V") (pinfunction "18_V") (pintype "bidirectional"))
      (node (ref "DRIVE") (pin "VV") (pinfunction "40_VV") (pintype "bidirectional"))
      (node (ref "DRIVE") (pin "W") (pinfunction "19_W") (pintype "bidirectional"))
      (node (ref "DRIVE") (pin "Y") (pinfunction "21_Y") (pintype "bidirectional"))
      (node (ref "DRIVE") (pin "Z") (pinfunction "22_Z") (pintype "bidirectional"))
      (node (ref "E11") (pin "10") (pinfunction "I1_10") (pintype "input"))
      (node (ref "E11") (pin "5") (pinfunction "I1_5") (pintype "input"))
      (node (ref "E11") (pin "7") (pinfunction "I1_7") (pintype "input"))
      (node (ref "E39") (pin "7") (pinfunction "I1_7") (pintype "input"))
      (node (ref "E4") (pin "6") (pinfunction "D_6") (pintype "input"))
      (node (ref "R10") (pin "1") (pinfunction "1_1") (pintype "passive"))
      (node (ref "R11") (pin "1") (pinfunction "1_1") (pintype "passive"))
      (node (ref "R12") (pin "1") (pinfunction "1_1") (pintype "passive"))
      (node (ref "R13") (pin "1") (pinfunction "1_1") (pintype "passive"))
      (node (ref "R14") (pin "1") (pinfunction "1_1") (pintype "passive"))
      (node (ref "R15") (pin "1") (pinfunction "1_1") (pintype "passive"))
      (node (ref "R16") (pin "1") (pinfunction "1_1") (pintype "passive"))
      (node (ref "R17") (pin "1") (pinfunction "1_1") (pintype "passive"))
      (node (ref "U$2") (pin "AC2") (pinfunction "1_AC2") (pintype "bidirectional"))
      (node (ref "U$2") (pin "AT1") (pinfunction "1_AT1") (pintype "bidirectional"))
      (node (ref "U$2") (pin "AT2") (pinfunction "1_AT2") (pintype "bidirectional"))
      (node (ref "U$2") (pin "BC2") (pinfunction "1_BC2") (pintype "bidirectional"))
      (node (ref "U$2") (pin "BT1") (pinfunction "1_BT1") (pintype "bidirectional"))
      (node (ref "U$2") (pin "CC2") (pinfunction "1_CC2") (pintype "bidirectional"))
      (node (ref "U$2") (pin "CT1") (pinfunction "1_CT1") (pintype "bidirectional"))
      (node (ref "U$2") (pin "DC2") (pinfunction "1_DC2") (pintype "bidirectional"))
      (node (ref "U$2") (pin "DT1") (pinfunction "1_DT1") (pintype "bidirectional"))
    )
    (net (code "23") (name "INIT") (class "Default")
      (node (ref "E19") (pin "6") (pinfunction "I1_6") (pintype "input"))
      (node (ref "E23") (pin "3") (pinfunction "I1_3") (pintype "input"))
      (node (ref "E23") (pin "6") (pinfunction "I1_6") (pintype "input"))
      (node (ref "E24") (pin "3") (pinfunction "O_3") (pintype "output"))
      (node (ref "E32") (pin "3") (pinfunction "I_3") (pintype "input"))
      (node (ref "E37") (pin "11") (pinfunction "I0_11") (pintype "input"))
      (node (ref "E37") (pin "12") (pinfunction "I1_12") (pintype "input"))
      (node (ref "E6") (pin "12") (pinfunction "I1_12") (pintype "input"))
      (node (ref "E8") (pin "5") (pinfunction "I_5") (pintype "input"))
    )
    (net (code "24") (name "INITIALIZE") (class "Default")
      (node (ref "E11") (pin "6") (pinfunction "I0_6") (pintype "input"))
      (node (ref "U$2") (pin "CR1") (pinfunction "1_CR1") (pintype "bidirectional"))
    )
    (net (code "25") (name "LCD_IOT") (class "Default")
      (node (ref "E12") (pin "10") (pinfunction "I1_10") (pintype "input"))
      (node (ref "E28") (pin "4") (pinfunction "I2_4") (pintype "input"))
      (node (ref "E38") (pin "4") (pinfunction "O_4") (pintype "output"))
    )
    (net (code "26") (name "MAINT") (class "Default")
      (node (ref "E2") (pin "9") (pinfunction "Q_9") (pintype "output"))
      (node (ref "E20") (pin "9") (pinfunction "I0_9") (pintype "input"))
    )
    (net (code "27") (name "MSB8") (class "Default")
      (node (ref "E17") (pin "3") (pinfunction "I1_3") (pintype "input"))
      (node (ref "E21") (pin "11") (pinfunction "QD_11") (pintype "output"))
      (node (ref "E3") (pin "5") (pinfunction "I2_5") (pintype "input"))
      (node (ref "E9") (pin "4") (pinfunction "SER_4") (pintype "input"))
    )
    (net (code "28") (name "MSB12") (class "Default")
      (node (ref "E3") (pin "2") (pinfunction "I1_2") (pintype "input"))
      (node (ref "E5") (pin "3") (pinfunction "I1_3") (pintype "input"))
      (node (ref "E9") (pin "11") (pinfunction "QD_11") (pintype "output"))
    )
    (net (code "29") (name "Net-(E2A-CLK)") (class "Default")
      (node (ref "E2") (pin "11") (pinfunction "CLK_11") (pintype "input"))
      (node (ref "E2") (pin "3") (pinfunction "CLK_3") (pintype "input"))
      (node (ref "E6") (pin "1") (pinfunction "O_1") (pintype "output"))
    )
    (net (code "30") (name "Net-(E3A-I2)") (class "Default")
      (node (ref "E3") (pin "13") (pinfunction "I2_13") (pintype "input"))
      (node (ref "E3") (pin "3") (pinfunction "I0_3") (pintype "input"))
      (node (ref "E8") (pin "2") (pinfunction "O_2") (pintype "output"))
    )
    (net (code "31") (name "Net-(E3A-O)") (class "Default")
      (node (ref "E3") (pin "11") (pinfunction "I2_11") (pintype "input"))
      (node (ref "E3") (pin "12") (pinfunction "O_12") (pintype "output"))
    )
    (net (code "32") (name "Net-(E3B-O)") (class "Default")
      (node (ref "E3") (pin "6") (pinfunction "O_6") (pintype "output"))
      (node (ref "E3") (pin "9") (pinfunction "I0_9") (pintype "input"))
    )
    (net (code "33") (name "Net-(E4A-CLK)") (class "Default")
      (node (ref "E4") (pin "2") (pinfunction "CLK_2") (pintype "input"))
      (node (ref "E8") (pin "13") (pinfunction "I_13") (pintype "input"))
      (node (ref "E8") (pin "4") (pinfunction "O_4") (pintype "output"))
    )
    (net (code "34") (name "Net-(E5B-I1)") (class "Default")
      (node (ref "E5") (pin "6") (pinfunction "I1_6") (pintype "input"))
      (node (ref "E9") (pin "9") (pinfunction "QC_9") (pintype "output"))
    )
    (net (code "35") (name "Net-(E5C-I1)") (class "Default")
      (node (ref "E5") (pin "9") (pinfunction "I1_9") (pintype "input"))
      (node (ref "E9") (pin "7") (pinfunction "QB_7") (pintype "output"))
    )
    (net (code "36") (name "Net-(E5D-I1)") (class "Default")
      (node (ref "E5") (pin "12") (pinfunction "I1_12") (pintype "input"))
      (node (ref "E9") (pin "5") (pinfunction "QA_5") (pintype "output"))
    )
    (net (code "37") (name "Net-(E10A-I1)") (class "Default")
      (node (ref "E10") (pin "2") (pinfunction "I1_2") (pintype "input"))
      (node (ref "E10") (pin "6") (pinfunction "O_6") (pintype "output"))
      (node (ref "E14") (pin "12") (pinfunction "I1_12") (pintype "input"))
    )
    (net (code "38") (name "Net-(E10A-O)") (class "Default")
      (node (ref "E10") (pin "12") (pinfunction "O_12") (pintype "output"))
      (node (ref "E12") (pin "5") (pinfunction "I1_5") (pintype "input"))
    )
    (net (code "39") (name "Net-(E10C-O)") (class "Default")
      (node (ref "E10") (pin "8") (pinfunction "O_8") (pintype "output"))
      (node (ref "E18") (pin "8") (pinfunction "I0_8") (pintype "input"))
      (node (ref "E18") (pin "9") (pinfunction "I1_9") (pintype "input"))
    )
    (net (code "40") (name "Net-(E11A-O)") (class "Default")
      (node (ref "E11") (pin "3") (pinfunction "O_3") (pintype "output"))
      (node (ref "E7") (pin "4") (pinfunction "PRE_4") (pintype "input"))
      (node (ref "E8") (pin "9") (pinfunction "I_9") (pintype "input"))
    )
    (net (code "41") (name "Net-(E11B-O)") (class "Default")
      (node (ref "E11") (pin "2") (pinfunction "O_2") (pintype "output"))
      (node (ref "E24") (pin "1") (pinfunction "I0_1") (pintype "input"))
    )
    (net (code "42") (name "Net-(E12A-I0)") (class "Default")
      (node (ref "E12") (pin "1") (pinfunction "I0_1") (pintype "input"))
      (node (ref "E12") (pin "11") (pinfunction "O_11") (pintype "output"))
    )
    (net (code "43") (name "Net-(E12A-I1)") (class "Default")
      (node (ref "E12") (pin "2") (pinfunction "I1_2") (pintype "input"))
      (node (ref "E12") (pin "8") (pinfunction "O_8") (pintype "output"))
    )
    (net (code "44") (name "Net-(E12A-O)") (class "Default")
      (node (ref "E12") (pin "3") (pinfunction "O_3") (pintype "output"))
      (node (ref "E4") (pin "5") (pinfunction "C_5") (pintype "input"))
    )
    (net (code "45") (name "Net-(E12B-O)") (class "Default")
      (node (ref "E12") (pin "6") (pinfunction "O_6") (pintype "output"))
      (node (ref "E14") (pin "2") (pinfunction "I0_2") (pintype "input"))
      (node (ref "E14") (pin "3") (pinfunction "I1_3") (pintype "input"))
    )
    (net (code "46") (name "Net-(E14B-I1)") (class "Default")
      (node (ref "E14") (pin "6") (pinfunction "I1_6") (pintype "input"))
      (node (ref "E27") (pin "16") (pinfunction "K_16") (pintype "input"))
      (node (ref "E27") (pin "4") (pinfunction "J_4") (pintype "input"))
      (node (ref "E3") (pin "8") (pinfunction "O_8") (pintype "output"))
    )
    (net (code "47") (name "Net-(E15A-CLK)") (class "Default")
      (node (ref "E15") (pin "3") (pinfunction "CLK_3") (pintype "input"))
      (node (ref "E6") (pin "4") (pinfunction "O_4") (pintype "output"))
    )
    (net (code "48") (name "Net-(E15A-Q)") (class "Default")
      (node (ref "E15") (pin "5") (pinfunction "Q_5") (pintype "output"))
      (node (ref "E18") (pin "5") (pinfunction "I0_5") (pintype "input"))
    )
    (net (code "49") (name "Net-(E15B-CLK)") (class "Default")
      (node (ref "E15") (pin "11") (pinfunction "CLK_11") (pintype "input"))
      (node (ref "E24") (pin "6") (pinfunction "O_6") (pintype "output"))
    )
    (net (code "50") (name "Net-(E15B-CLR)") (class "Default")
      (node (ref "E15") (pin "13") (pinfunction "CLR_13") (pintype "input"))
      (node (ref "E16") (pin "8") (pinfunction "O_8") (pintype "output"))
    )
    (net (code "51") (name "Net-(E16A-I1)") (class "Default")
      (node (ref "E16") (pin "2") (pinfunction "I1_2") (pintype "input"))
      (node (ref "E17") (pin "11") (pinfunction "I0_11") (pintype "input"))
      (node (ref "E17") (pin "2") (pinfunction "I0_2") (pintype "input"))
      (node (ref "E17") (pin "5") (pinfunction "I0_5") (pintype "input"))
      (node (ref "E17") (pin "8") (pinfunction "I0_8") (pintype "input"))
      (node (ref "E19") (pin "13") (pinfunction "O_13") (pintype "output"))
      (node (ref "E29") (pin "11") (pinfunction "I0_11") (pintype "input"))
      (node (ref "E29") (pin "2") (pinfunction "I0_2") (pintype "input"))
      (node (ref "E29") (pin "5") (pinfunction "I0_5") (pintype "input"))
      (node (ref "E29") (pin "8") (pinfunction "I0_8") (pintype "input"))
    )
    (net (code "52") (name "Net-(E16A-O)") (class "Default")
      (node (ref "E16") (pin "3") (pinfunction "O_3") (pintype "output"))
      (node (ref "E5") (pin "11") (pinfunction "I0_11") (pintype "input"))
      (node (ref "E5") (pin "2") (pinfunction "I0_2") (pintype "input"))
      (node (ref "E5") (pin "5") (pinfunction "I0_5") (pintype "input"))
      (node (ref "E5") (pin "8") (pinfunction "I0_8") (pintype "input"))
    )
    (net (code "53") (name "Net-(E16B-O)") (class "Default")
      (node (ref "E16") (pin "6") (pinfunction "O_6") (pintype "output"))
      (node (ref "E20") (pin "2") (pinfunction "I1_2") (pintype "input"))
    )
    (net (code "54") (name "Net-(E16C-I0)") (class "Default")
      (node (ref "E16") (pin "9") (pinfunction "I0_9") (pintype "input"))
      (node (ref "E24") (pin "9") (pinfunction "I0_9") (pintype "input"))
      (node (ref "E39") (pin "13") (pinfunction "O_13") (pintype "output"))
    )
    (net (code "55") (name "Net-(E16D-I1)") (class "Default")
      (node (ref "E16") (pin "13") (pinfunction "I1_13") (pintype "input"))
      (node (ref "E24") (pin "8") (pinfunction "O_8") (pintype "output"))
    )
    (net (code "56") (name "Net-(E17B-I1)") (class "Default")
      (node (ref "E17") (pin "6") (pinfunction "I1_6") (pintype "input"))
      (node (ref "E21") (pin "9") (pinfunction "QC_9") (pintype "output"))
    )
    (net (code "57") (name "Net-(E17C-I1)") (class "Default")
      (node (ref "E17") (pin "9") (pinfunction "I1_9") (pintype "input"))
      (node (ref "E21") (pin "7") (pinfunction "QB_7") (pintype "output"))
    )
    (net (code "58") (name "Net-(E17D-I1)") (class "Default")
      (node (ref "E17") (pin "12") (pinfunction "I1_12") (pintype "input"))
      (node (ref "E21") (pin "5") (pinfunction "QA_5") (pintype "output"))
    )
    (net (code "59") (name "Net-(E18A-I0)") (class "Default")
      (node (ref "E18") (pin "2") (pinfunction "I0_2") (pintype "input"))
      (node (ref "E18") (pin "3") (pinfunction "I1_3") (pintype "input"))
      (node (ref "E32") (pin "5") (pinfunction "I_5") (pintype "input"))
      (node (ref "E35") (pin "3") (pinfunction "O_3") (pintype "output"))
      (node (ref "E38") (pin "1") (pinfunction "I_1") (pintype "input"))
    )
    (net (code "60") (name "Net-(E18B-I1)") (class "Default")
      (node (ref "E18") (pin "6") (pinfunction "I1_6") (pintype "input"))
      (node (ref "E22") (pin "9") (pinfunction "Q_9") (pintype "output"))
      (node (ref "E34") (pin "13") (pinfunction "I1_13") (pintype "input"))
    )
    (net (code "61") (name "Net-(E19A-I0)") (class "Default")
      (node (ref "E19") (pin "2") (pinfunction "I0_2") (pintype "input"))
      (node (ref "E20") (pin "12") (pinfunction "O_12") (pintype "output"))
    )
    (net (code "62") (name "Net-(E19B-I0)") (class "Default")
      (node (ref "E19") (pin "10") (pinfunction "O_10") (pintype "output"))
      (node (ref "E19") (pin "5") (pinfunction "I0_5") (pintype "input"))
    )
    (net (code "63") (name "Net-(E19B-O)") (class "Default")
      (node (ref "E19") (pin "4") (pinfunction "O_4") (pintype "output"))
      (node (ref "E22") (pin "1") (pinfunction "CLR_1") (pintype "input"))
    )
    (net (code "64") (name "Net-(E19D-I0)") (class "Default")
      (node (ref "E19") (pin "11") (pinfunction "I0_11") (pintype "input"))
      (node (ref "E20") (pin "8") (pinfunction "O_8") (pintype "output"))
    )
    (net (code "65") (name "Net-(E21A-SER)") (class "Default")
      (node (ref "E21") (pin "4") (pinfunction "SER_4") (pintype "input"))
      (node (ref "E29") (pin "3") (pinfunction "I1_3") (pintype "input"))
      (node (ref "E33") (pin "11") (pinfunction "QD_11") (pintype "output"))
    )
    (net (code "66") (name "Net-(E22A-Q)") (class "Default")
      (node (ref "E22") (pin "12") (pinfunction "D_12") (pintype "input"))
      (node (ref "E22") (pin "5") (pinfunction "Q_5") (pintype "output"))
    )
    (net (code "67") (name "Net-(E23A-I0)") (class "Default")
      (node (ref "E23") (pin "13") (pinfunction "O_13") (pintype "output"))
      (node (ref "E23") (pin "2") (pinfunction "I0_2") (pintype "input"))
    )
    (net (code "68") (name "Net-(E23A-O)") (class "Default")
      (node (ref "E23") (pin "1") (pinfunction "O_1") (pintype "output"))
      (node (ref "E30") (pin "1") (pinfunction "CLR_1") (pintype "input"))
    )
    (net (code "69") (name "Net-(E23B-I0)") (class "Default")
      (node (ref "E23") (pin "10") (pinfunction "O_10") (pintype "output"))
      (node (ref "E23") (pin "5") (pinfunction "I0_5") (pintype "input"))
    )
    (net (code "70") (name "Net-(E23B-O)") (class "Default")
      (node (ref "E23") (pin "4") (pinfunction "O_4") (pintype "output"))
      (node (ref "E26") (pin "1") (pinfunction "CLR_1") (pintype "input"))
    )
    (net (code "71") (name "Net-(E24A-I1)") (class "Default")
      (node (ref "E24") (pin "2") (pinfunction "I1_2") (pintype "input"))
      (node (ref "E7") (pin "5") (pinfunction "Q_5") (pintype "output"))
    )
    (net (code "72") (name "Net-(E24B-I0)") (class "Default")
      (node (ref "E24") (pin "4") (pinfunction "I0_4") (pintype "input"))
      (node (ref "E28") (pin "8") (pinfunction "O_8") (pintype "output"))
    )
    (net (code "73") (name "Net-(E24B-I1)") (class "Default")
      (node (ref "E24") (pin "5") (pinfunction "I1_5") (pintype "input"))
      (node (ref "E28") (pin "6") (pinfunction "O_6") (pintype "output"))
    )
    (net (code "74") (name "Net-(E24D-O)") (class "Default")
      (node (ref "E24") (pin "11") (pinfunction "O_11") (pintype "output"))
      (node (ref "E3") (pin "10") (pinfunction "I1_10") (pintype "input"))
    )
    (net (code "75") (name "Net-(E26A-Q)") (class "Default")
      (node (ref "E26") (pin "12") (pinfunction "D_12") (pintype "input"))
      (node (ref "E26") (pin "5") (pinfunction "Q_5") (pintype "output"))
    )
    (net (code "76") (name "Net-(E26B-Q)") (class "Default")
      (node (ref "E26") (pin "9") (pinfunction "Q_9") (pintype "output"))
      (node (ref "E34") (pin "1") (pinfunction "I0_1") (pintype "input"))
    )
    (net (code "77") (name "Net-(E27A-CLR)") (class "Default")
      (node (ref "E27") (pin "3") (pinfunction "CLR_3") (pintype "input"))
      (node (ref "E6") (pin "13") (pinfunction "O_13") (pintype "output"))
    )
    (net (code "78") (name "Net-(E29B-I1)") (class "Default")
      (node (ref "E29") (pin "6") (pinfunction "I1_6") (pintype "input"))
      (node (ref "E33") (pin "9") (pinfunction "QC_9") (pintype "output"))
    )
    (net (code "79") (name "Net-(E29C-I1)") (class "Default")
      (node (ref "E29") (pin "9") (pinfunction "I1_9") (pintype "input"))
      (node (ref "E33") (pin "7") (pinfunction "QB_7") (pintype "output"))
    )
    (net (code "80") (name "Net-(E29D-I1)") (class "Default")
      (node (ref "E29") (pin "12") (pinfunction "I1_12") (pintype "input"))
      (node (ref "E33") (pin "5") (pinfunction "QA_5") (pintype "output"))
    )
    (net (code "81") (name "Net-(E30A-Q)") (class "Default")
      (node (ref "E30") (pin "12") (pinfunction "D_12") (pintype "input"))
      (node (ref "E30") (pin "5") (pinfunction "Q_5") (pintype "output"))
    )
    (net (code "82") (name "Net-(E30B-Q)") (class "Default")
      (node (ref "E30") (pin "9") (pinfunction "Q_9") (pintype "output"))
      (node (ref "E34") (pin "10") (pinfunction "I1_10") (pintype "input"))
    )
    (net (code "83") (name "Net-(E34A-I1)") (class "Default")
      (node (ref "E34") (pin "2") (pinfunction "I1_2") (pintype "input"))
      (node (ref "E38") (pin "8") (pinfunction "O_8") (pintype "output"))
    )
    (net (code "84") (name "Net-(E34C-I0)") (class "Default")
      (node (ref "E34") (pin "9") (pinfunction "I0_9") (pintype "input"))
      (node (ref "E38") (pin "12") (pinfunction "O_12") (pintype "output"))
    )
    (net (code "85") (name "Net-(E34D-I0)") (class "Default")
      (node (ref "E34") (pin "12") (pinfunction "I0_12") (pintype "input"))
      (node (ref "E38") (pin "10") (pinfunction "O_10") (pintype "output"))
    )
    (net (code "86") (name "Net-(E35A-I3)") (class "Default")
      (node (ref "E35") (pin "9") (pinfunction "I3_9") (pintype "input"))
      (node (ref "E39") (pin "2") (pinfunction "O_2") (pintype "output"))
      (node (ref "E40") (pin "7") (pinfunction "FORCE0_7") (pintype "input"))
    )
    (net (code "87") (name "Net-(E35A-I4)") (class "Default")
      (node (ref "E31") (pin "11") (pinfunction "11_11") (pintype "passive"))
      (node (ref "E31") (pin "14") (pinfunction "14_14") (pintype "passive"))
      (node (ref "E35") (pin "10") (pinfunction "I4_10") (pintype "input"))
    )
    (net (code "88") (name "Net-(E35A-I5)") (class "Default")
      (node (ref "E31") (pin "12") (pinfunction "12_12") (pintype "passive"))
      (node (ref "E31") (pin "15") (pinfunction "15_15") (pintype "passive"))
      (node (ref "E35") (pin "11") (pinfunction "I5_11") (pintype "input"))
    )
    (net (code "89") (name "Net-(E35A-I6)") (class "Default")
      (node (ref "E31") (pin "13") (pinfunction "13_13") (pintype "passive"))
      (node (ref "E31") (pin "16") (pinfunction "16_16") (pintype "passive"))
      (node (ref "E35") (pin "12") (pinfunction "I6_12") (pintype "input"))
    )
    (net (code "90") (name "Net-(E38A-O)") (class "Default")
      (node (ref "E38") (pin "2") (pinfunction "O_2") (pintype "output"))
      (node (ref "E40") (pin "9") (pinfunction "FORCE0_9") (pintype "input"))
      (node (ref "E41") (pin "12") (pinfunction "D_12") (pintype "input"))
    )
    (net (code "91") (name "Net-(E40A-A1)") (class "Default")
      (node (ref "E31") (pin "1") (pinfunction "1_1") (pintype "passive"))
      (node (ref "E40") (pin "2") (pinfunction "A1_2") (pintype "output"))
    )
    (net (code "92") (name "Net-(E40A-A2)") (class "Default")
      (node (ref "E31") (pin "2") (pinfunction "2_2") (pintype "passive"))
      (node (ref "E40") (pin "4") (pinfunction "A2_4") (pintype "output"))
    )
    (net (code "93") (name "Net-(E40A-A3)") (class "Default")
      (node (ref "E31") (pin "3") (pinfunction "3_3") (pintype "passive"))
      (node (ref "E40") (pin "6") (pinfunction "A3_6") (pintype "output"))
    )
    (net (code "94") (name "Net-(E40B-A1)") (class "Default")
      (node (ref "E40") (pin "10") (pinfunction "A1_10") (pintype "output"))
      (node (ref "E41") (pin "15") (pinfunction "A_15") (pintype "input"))
    )
    (net (code "95") (name "Net-(E40B-A2)") (class "Default")
      (node (ref "E40") (pin "12") (pinfunction "A2_12") (pintype "output"))
      (node (ref "E41") (pin "14") (pinfunction "B_14") (pintype "input"))
    )
    (net (code "96") (name "Net-(E40B-A3)") (class "Default")
      (node (ref "E40") (pin "14") (pinfunction "A3_14") (pintype "output"))
      (node (ref "E41") (pin "13") (pinfunction "C_13") (pintype "input"))
    )
    (net (code "97") (name "Net-(PAD10-P)") (class "Default")
      (node (ref "E13") (pin "1") (pinfunction "1_1") (pintype "passive"))
      (node (ref "PAD10") (pin "1") (pinfunction "P_1") (pintype "passive"))
    )
    (net (code "98") (name "Net-(PAD11-P)") (class "Default")
      (node (ref "E13") (pin "2") (pinfunction "2_2") (pintype "passive"))
      (node (ref "PAD11") (pin "1") (pinfunction "P_1") (pintype "passive"))
    )
    (net (code "99") (name "Net-(PAD12-P)") (class "Default")
      (node (ref "E13") (pin "3") (pinfunction "3_3") (pintype "passive"))
      (node (ref "PAD12") (pin "1") (pinfunction "P_1") (pintype "passive"))
    )
    (net (code "100") (name "Net-(PAD13-P)") (class "Default")
      (node (ref "E13") (pin "4") (pinfunction "4_4") (pintype "passive"))
      (node (ref "PAD13") (pin "1") (pinfunction "P_1") (pintype "passive"))
    )
    (net (code "101") (name "Net-(PAD14-P)") (class "Default")
      (node (ref "E13") (pin "5") (pinfunction "5_5") (pintype "passive"))
      (node (ref "PAD14") (pin "1") (pinfunction "P_1") (pintype "passive"))
    )
    (net (code "102") (name "Net-(PAD15-P)") (class "Default")
      (node (ref "E13") (pin "6") (pinfunction "6_6") (pintype "passive"))
      (node (ref "PAD15") (pin "1") (pinfunction "P_1") (pintype "passive"))
    )
    (net (code "103") (name "Net-(PAD16-P)") (class "Default")
      (node (ref "E13") (pin "7") (pinfunction "7_7") (pintype "passive"))
      (node (ref "PAD16") (pin "1") (pinfunction "P_1") (pintype "passive"))
    )
    (net (code "104") (name "Net-(PAD17-P)") (class "Default")
      (node (ref "E13") (pin "8") (pinfunction "8_8") (pintype "passive"))
      (node (ref "PAD17") (pin "1") (pinfunction "P_1") (pintype "passive"))
    )
    (net (code "105") (name "Net-(PAD20-P)") (class "Default")
      (node (ref "E13") (pin "16") (pinfunction "16_16") (pintype "passive"))
      (node (ref "PAD20") (pin "1") (pinfunction "P_1") (pintype "passive"))
    )
    (net (code "106") (name "Net-(PAD21-P)") (class "Default")
      (node (ref "E13") (pin "15") (pinfunction "15_15") (pintype "passive"))
      (node (ref "PAD21") (pin "1") (pinfunction "P_1") (pintype "passive"))
    )
    (net (code "107") (name "Net-(PAD22-P)") (class "Default")
      (node (ref "E13") (pin "14") (pinfunction "14_14") (pintype "passive"))
      (node (ref "PAD22") (pin "1") (pinfunction "P_1") (pintype "passive"))
    )
    (net (code "108") (name "Net-(PAD23-P)") (class "Default")
      (node (ref "E13") (pin "13") (pinfunction "13_13") (pintype "passive"))
      (node (ref "PAD23") (pin "1") (pinfunction "P_1") (pintype "passive"))
    )
    (net (code "109") (name "Net-(PAD24-P)") (class "Default")
      (node (ref "E13") (pin "12") (pinfunction "12_12") (pintype "passive"))
      (node (ref "PAD24") (pin "1") (pinfunction "P_1") (pintype "passive"))
    )
    (net (code "110") (name "Net-(PAD25-P)") (class "Default")
      (node (ref "E13") (pin "11") (pinfunction "11_11") (pintype "passive"))
      (node (ref "PAD25") (pin "1") (pinfunction "P_1") (pintype "passive"))
    )
    (net (code "111") (name "Net-(PAD26-P)") (class "Default")
      (node (ref "E13") (pin "10") (pinfunction "10_10") (pintype "passive"))
      (node (ref "PAD26") (pin "1") (pinfunction "P_1") (pintype "passive"))
    )
    (net (code "112") (name "Net-(PAD27-P)") (class "Default")
      (node (ref "E13") (pin "9") (pinfunction "9_9") (pintype "passive"))
      (node (ref "PAD27") (pin "1") (pinfunction "P_1") (pintype "passive"))
    )
    (net (code "113") (name "PARITY") (class "Default")
      (node (ref "E24") (pin "13") (pinfunction "I1_13") (pintype "input"))
      (node (ref "E4") (pin "15") (pinfunction "RCO_15") (pintype "output"))
      (node (ref "E8") (pin "1") (pinfunction "I_1") (pintype "input"))
      (node (ref "U$2") (pin "AB1") (pinfunction "1_AB1") (pintype "bidirectional"))
    )
    (net (code "114") (name "RD") (class "Default")
      (node (ref "E20") (pin "10") (pinfunction "I1_10") (pintype "input"))
      (node (ref "E32") (pin "1") (pinfunction "I_1") (pintype "input"))
      (node (ref "E36") (pin "14") (pinfunction "A3_14") (pintype "output"))
    )
    (net (code "115") (name "RUN") (class "Default")
      (node (ref "E15") (pin "9") (pinfunction "Q_9") (pintype "output"))
      (node (ref "E18") (pin "11") (pinfunction "I0_11") (pintype "input"))
      (node (ref "E18") (pin "12") (pinfunction "I1_12") (pintype "input"))
      (node (ref "E6") (pin "11") (pinfunction "I0_11") (pintype "input"))
    )
    (net (code "116") (name "RX_DATA") (class "Default")
      (node (ref "E33") (pin "4") (pinfunction "SER_4") (pintype "input"))
      (node (ref "E36") (pin "10") (pinfunction "A1_10") (pintype "output"))
    )
    (net (code "117") (name "SHIFT") (class "Default")
      (node (ref "E19") (pin "3") (pinfunction "I1_3") (pintype "input"))
      (node (ref "E36") (pin "12") (pinfunction "A2_12") (pintype "output"))
    )
    (net (code "118") (name "TP3") (class "Default")
      (node (ref "E11") (pin "9") (pinfunction "I0_9") (pintype "input"))
      (node (ref "U$2") (pin "CH2") (pinfunction "1_CH2") (pintype "bidirectional"))
    )
    (net (code "119") (name "TP4") (class "Default")
      (node (ref "E11") (pin "4") (pinfunction "I0_4") (pintype "input"))
      (node (ref "U$2") (pin "CJ2") (pinfunction "1_CJ2") (pintype "bidirectional"))
    )
    (net (code "120") (name "VCC") (class "Default")
      (node (ref "C1") (pin "1") (pinfunction "1_1") (pintype "passive"))
      (node (ref "C10") (pin "1") (pinfunction "1_1") (pintype "passive"))
      (node (ref "C11") (pin "1") (pinfunction "1_1") (pintype "passive"))
      (node (ref "C12") (pin "1") (pinfunction "1_1") (pintype "passive"))
      (node (ref "C13") (pin "1") (pinfunction "1_1") (pintype "passive"))
      (node (ref "C14") (pin "1") (pinfunction "1_1") (pintype "passive"))
      (node (ref "C15") (pin "1") (pinfunction "1_1") (pintype "passive"))
      (node (ref "C16") (pin "1") (pinfunction "1_1") (pintype "passive"))
      (node (ref "C17") (pin "1") (pinfunction "1_1") (pintype "passive"))
      (node (ref "C18") (pin "1") (pinfunction "1_1") (pintype "passive"))
      (node (ref "C19") (pin "1") (pinfunction "1_1") (pintype "passive"))
      (node (ref "C2") (pin "1") (pinfunction "1_1") (pintype "passive"))
      (node (ref "C20") (pin "1") (pinfunction "1_1") (pintype "passive"))
      (node (ref "C21") (pin "1") (pinfunction "1_1") (pintype "passive"))
      (node (ref "C22") (pin "1") (pinfunction "1_1") (pintype "passive"))
      (node (ref "C23") (pin "1") (pinfunction "1_1") (pintype "passive"))
      (node (ref "C24") (pin "1") (pinfunction "1_1") (pintype "passive"))
      (node (ref "C25") (pin "1") (pinfunction "1_1") (pintype "passive"))
      (node (ref "C26") (pin "1") (pinfunction "1_1") (pintype "passive"))
      (node (ref "C27") (pin "1") (pinfunction "1_1") (pintype "passive"))
      (node (ref "C28") (pin "1") (pinfunction "1_1") (pintype "passive"))
      (node (ref "C29") (pin "1") (pinfunction "1_1") (pintype "passive"))
      (node (ref "C3") (pin "1") (pinfunction "1_1") (pintype "passive"))
      (node (ref "C30") (pin "1") (pinfunction "1_1") (pintype "passive"))
      (node (ref "C31") (pin "1") (pinfunction "1_1") (pintype "passive"))
      (node (ref "C32") (pin "1") (pinfunction "1_1") (pintype "passive"))
      (node (ref "C33") (pin "1") (pinfunction "1_1") (pintype "passive"))
      (node (ref "C34") (pin "1") (pinfunction "1_1") (pintype "passive"))
      (node (ref "C35") (pin "1") (pinfunction "1_1") (pintype "passive"))
      (node (ref "C36") (pin "1") (pinfunction "1_1") (pintype "passive"))
      (node (ref "C37") (pin "1") (pinfunction "1_1") (pintype "passive"))
      (node (ref "C38") (pin "1") (pinfunction "1_1") (pintype "passive"))
      (node (ref "C39") (pin "1") (pinfunction "1_1") (pintype "passive"))
      (node (ref "C4") (pin "1") (pinfunction "1_1") (pintype "passive"))
      (node (ref "C40") (pin "1") (pinfunction "1_1") (pintype "passive"))
      (node (ref "C41") (pin "1") (pinfunction "1_1") (pintype "passive"))
      (node (ref "C42") (pin "+") (pinfunction "+_+") (pintype "passive"))
      (node (ref "C43") (pin "+") (pinfunction "+_+") (pintype "passive"))
      (node (ref "C44") (pin "+") (pinfunction "+_+") (pintype "passive"))
      (node (ref "C45") (pin "+") (pinfunction "+_+") (pintype "passive"))
      (node (ref "C5") (pin "1") (pinfunction "1_1") (pintype "passive"))
      (node (ref "C6") (pin "1") (pinfunction "1_1") (pintype "passive"))
      (node (ref "C7") (pin "1") (pinfunction "1_1") (pintype "passive"))
      (node (ref "C8") (pin "1") (pinfunction "1_1") (pintype "passive"))
      (node (ref "C9") (pin "1") (pinfunction "1_1") (pintype "passive"))
      (node (ref "R1") (pin "2") (pinfunction "2_2") (pintype "passive"))
      (node (ref "R19") (pin "1") (pinfunction "1_1") (pintype "passive"))
      (node (ref "R2") (pin "2") (pinfunction "2_2") (pintype "passive"))
      (node (ref "R20") (pin "2") (pinfunction "2_2") (pintype "passive"))
      (node (ref "R3") (pin "2") (pinfunction "2_2") (pintype "passive"))
      (node (ref "R4") (pin "2") (pinfunction "2_2") (pintype "passive"))
      (node (ref "R5") (pin "2") (pinfunction "2_2") (pintype "passive"))
      (node (ref "R6") (pin "2") (pinfunction "2_2") (pintype "passive"))
      (node (ref "R7") (pin "2") (pinfunction "2_2") (pintype "passive"))
      (node (ref "R8") (pin "2") (pinfunction "2_2") (pintype "passive"))
      (node (ref "R9") (pin "2") (pinfunction "2_2") (pintype "passive"))
      (node (ref "U$2") (pin "AA2") (pinfunction "1_AA2") (pintype "bidirectional"))
      (node (ref "U$2") (pin "BA2") (pinfunction "1_BA2") (pintype "bidirectional"))
      (node (ref "U$2") (pin "CA2") (pinfunction "1_CA2") (pintype "bidirectional"))
    )
    (net (code "121") (name "WRT") (class "Default")
      (node (ref "E10") (pin "5") (pinfunction "I2_5") (pintype "input"))
      (node (ref "E14") (pin "5") (pinfunction "I0_5") (pintype "input"))
      (node (ref "E24") (pin "10") (pinfunction "I1_10") (pintype "input"))
      (node (ref "E32") (pin "2") (pinfunction "O_2") (pintype "output"))
    )
    (net (code "122") (name "XFER_IOT") (class "Default")
      (node (ref "E10") (pin "1") (pinfunction "I0_1") (pintype "input"))
      (node (ref "E12") (pin "12") (pinfunction "I0_12") (pintype "input"))
      (node (ref "E28") (pin "9") (pinfunction "I0_9") (pintype "input"))
      (node (ref "E38") (pin "6") (pinfunction "O_6") (pintype "output"))
    )
    (net (code "123") (name "XFER_REQ") (class "Default")
      (node (ref "E30") (pin "3") (pinfunction "CLK_3") (pintype "input"))
      (node (ref "E36") (pin "4") (pinfunction "A2_4") (pintype "output"))
      (node (ref "E39") (pin "12") (pinfunction "I1_12") (pintype "input"))
    )
    (net (code "124") (name "unconnected-(E4A-QA-Pad14)") (class "Default")
      (node (ref "E4") (pin "14") (pinfunction "QA_14") (pintype "output"))
    )
    (net (code "125") (name "unconnected-(E4A-QB-Pad13)") (class "Default")
      (node (ref "E4") (pin "13") (pinfunction "QB_13") (pintype "output"))
    )
    (net (code "126") (name "unconnected-(E4A-QC-Pad12)") (class "Default")
      (node (ref "E4") (pin "12") (pinfunction "QC_12") (pintype "output"))
    )
    (net (code "127") (name "unconnected-(E4A-QD-Pad11)") (class "Default")
      (node (ref "E4") (pin "11") (pinfunction "QD_11") (pintype "output"))
    )
    (net (code "128") (name "unconnected-(E7A-~{Q}-Pad6)") (class "Default")
      (node (ref "E7") (pin "6") (pinfunction "~{Q}_6") (pintype "output"))
    )
    (net (code "129") (name "unconnected-(E9A-~{QD}-Pad12)") (class "Default")
      (node (ref "E9") (pin "12") (pinfunction "~{QD}_12") (pintype "output"))
    )
    (net (code "130") (name "unconnected-(E15A-~{Q}-Pad6)") (class "Default")
      (node (ref "E15") (pin "6") (pinfunction "~{Q}_6") (pintype "output"))
    )
    (net (code "131") (name "unconnected-(E15B-~{Q}-Pad8)") (class "Default")
      (node (ref "E15") (pin "8") (pinfunction "~{Q}_8") (pintype "output"))
    )
    (net (code "132") (name "unconnected-(E21A-~{QD}-Pad12)") (class "Default")
      (node (ref "E21") (pin "12") (pinfunction "~{QD}_12") (pintype "output"))
    )
    (net (code "133") (name "unconnected-(E22A-~{Q}-Pad6)") (class "Default")
      (node (ref "E22") (pin "6") (pinfunction "~{Q}_6") (pintype "output"))
    )
    (net (code "134") (name "unconnected-(E22B-~{Q}-Pad8)") (class "Default")
      (node (ref "E22") (pin "8") (pinfunction "~{Q}_8") (pintype "output"))
    )
    (net (code "135") (name "unconnected-(E26A-~{Q}-Pad6)") (class "Default")
      (node (ref "E26") (pin "6") (pinfunction "~{Q}_6") (pintype "output"))
    )
    (net (code "136") (name "unconnected-(E26B-~{Q}-Pad8)") (class "Default")
      (node (ref "E26") (pin "8") (pinfunction "~{Q}_8") (pintype "output"))
    )
    (net (code "137") (name "unconnected-(E27A-Q-Pad15)") (class "Default")
      (node (ref "E27") (pin "15") (pinfunction "Q_15") (pintype "output"))
    )
    (net (code "138") (name "unconnected-(E30A-~{Q}-Pad6)") (class "Default")
      (node (ref "E30") (pin "6") (pinfunction "~{Q}_6") (pintype "output"))
    )
    (net (code "139") (name "unconnected-(E30B-~{Q}-Pad8)") (class "Default")
      (node (ref "E30") (pin "8") (pinfunction "~{Q}_8") (pintype "output"))
    )
    (net (code "140") (name "unconnected-(E31-Pad7)") (class "Default")
      (node (ref "E31") (pin "7") (pinfunction "7_7") (pintype "passive"))
    )
    (net (code "141") (name "unconnected-(E31-Pad8)") (class "Default")
      (node (ref "E31") (pin "8") (pinfunction "8_8") (pintype "passive"))
    )
    (net (code "142") (name "unconnected-(E31-Pad9)") (class "Default")
      (node (ref "E31") (pin "9") (pinfunction "9_9") (pintype "passive"))
    )
    (net (code "143") (name "unconnected-(E31-Pad10)") (class "Default")
      (node (ref "E31") (pin "10") (pinfunction "10_10") (pintype "passive"))
    )
    (net (code "144") (name "unconnected-(E33A-~{QD}-Pad12)") (class "Default")
      (node (ref "E33") (pin "12") (pinfunction "~{QD}_12") (pintype "output"))
    )
    (net (code "145") (name "unconnected-(E41A-O0-Pad1)") (class "Default")
      (node (ref "E41") (pin "1") (pinfunction "O0_1") (pintype "output"))
    )
    (net (code "146") (name "unconnected-(E41A-O8-Pad10)") (class "Default")
      (node (ref "E41") (pin "10") (pinfunction "O8_10") (pintype "output"))
    )
    (net (code "147") (name "unconnected-(E41A-O9-Pad11)") (class "Default")
      (node (ref "E41") (pin "11") (pinfunction "O9_11") (pintype "output"))
    )
    (net (code "148") (name "~{BINIT}") (class "Default")
      (node (ref "E15") (pin "1") (pinfunction "CLR_1") (pintype "input"))
      (node (ref "E22") (pin "13") (pinfunction "CLR_13") (pintype "input"))
      (node (ref "E26") (pin "13") (pinfunction "CLR_13") (pintype "input"))
      (node (ref "E30") (pin "13") (pinfunction "CLR_13") (pintype "input"))
      (node (ref "E32") (pin "4") (pinfunction "O_4") (pintype "output"))
    )
    (net (code "149") (name "~{C0}") (class "Default")
      (node (ref "E14") (pin "1") (pinfunction "O_1") (pintype "open_collector"))
      (node (ref "U$2") (pin "CE1") (pinfunction "1_CE1") (pintype "bidirectional"))
    )
    (net (code "150") (name "~{C1}") (class "Default")
      (node (ref "E14") (pin "13") (pinfunction "O_13") (pintype "open_collector"))
      (node (ref "U$2") (pin "CH1") (pinfunction "1_CH1") (pintype "bidirectional"))
    )
    (net (code "151") (name "~{CLK_BUF}") (class "Default")
      (node (ref "E21") (pin "6") (pinfunction "CLK_6") (pintype "input"))
      (node (ref "E33") (pin "6") (pinfunction "CLK_6") (pintype "input"))
      (node (ref "E8") (pin "12") (pinfunction "O_12") (pintype "output"))
      (node (ref "E9") (pin "6") (pinfunction "CLK_6") (pintype "input"))
    )
    (net (code "152") (name "~{CLK_PARITY}") (class "Default")
      (node (ref "E19") (pin "1") (pinfunction "O_1") (pintype "output"))
      (node (ref "E27") (pin "1") (pinfunction "CLK_1") (pintype "input"))
      (node (ref "E8") (pin "3") (pinfunction "I_3") (pintype "input"))
    )
    (net (code "153") (name "~{DATA0}") (class "Default")
      (node (ref "E1") (pin "15") (pinfunction "Y3_15") (pintype "input"))
      (node (ref "E5") (pin "1") (pinfunction "O_1") (pintype "open_collector"))
      (node (ref "U$2") (pin "AR1") (pinfunction "1_AR1") (pintype "bidirectional"))
    )
    (net (code "154") (name "~{DATA1}") (class "Default")
      (node (ref "E1") (pin "13") (pinfunction "Y2_13") (pintype "input"))
      (node (ref "E5") (pin "4") (pinfunction "O_4") (pintype "open_collector"))
      (node (ref "U$2") (pin "AS1") (pinfunction "1_AS1") (pintype "bidirectional"))
    )
    (net (code "155") (name "~{DATA2}") (class "Default")
      (node (ref "E1") (pin "11") (pinfunction "Y1_11") (pintype "input"))
      (node (ref "E5") (pin "10") (pinfunction "O_10") (pintype "open_collector"))
      (node (ref "U$2") (pin "AU1") (pinfunction "1_AU1") (pintype "bidirectional"))
    )
    (net (code "156") (name "~{DATA3}") (class "Default")
      (node (ref "E1") (pin "5") (pinfunction "Y3_5") (pintype "input"))
      (node (ref "E5") (pin "13") (pinfunction "O_13") (pintype "open_collector"))
      (node (ref "U$2") (pin "AV1") (pinfunction "1_AV1") (pintype "bidirectional"))
    )
    (net (code "157") (name "~{DATA4}") (class "Default")
      (node (ref "E1") (pin "3") (pinfunction "Y2_3") (pintype "input"))
      (node (ref "E17") (pin "1") (pinfunction "O_1") (pintype "open_collector"))
      (node (ref "U$2") (pin "BR1") (pinfunction "1_BR1") (pintype "bidirectional"))
    )
    (net (code "158") (name "~{DATA5}") (class "Default")
      (node (ref "E1") (pin "1") (pinfunction "Y1_1") (pintype "input"))
      (node (ref "E17") (pin "4") (pinfunction "O_4") (pintype "open_collector"))
      (node (ref "U$2") (pin "BS1") (pinfunction "1_BS1") (pintype "bidirectional"))
    )
    (net (code "159") (name "~{DATA6}") (class "Default")
      (node (ref "E17") (pin "10") (pinfunction "O_10") (pintype "open_collector"))
      (node (ref "E25") (pin "15") (pinfunction "Y3_15") (pintype "input"))
      (node (ref "U$2") (pin "BU1") (pinfunction "1_BU1") (pintype "bidirectional"))
    )
    (net (code "160") (name "~{DATA7}") (class "Default")
      (node (ref "E17") (pin "13") (pinfunction "O_13") (pintype "open_collector"))
      (node (ref "E25") (pin "13") (pinfunction "Y2_13") (pintype "input"))
      (node (ref "U$2") (pin "BV1") (pinfunction "1_BV1") (pintype "bidirectional"))
    )
    (net (code "161") (name "~{DATA8}") (class "Default")
      (node (ref "E25") (pin "11") (pinfunction "Y1_11") (pintype "input"))
      (node (ref "E29") (pin "1") (pinfunction "O_1") (pintype "open_collector"))
      (node (ref "U$2") (pin "DR1") (pinfunction "1_DR1") (pintype "bidirectional"))
    )
    (net (code "162") (name "~{DATA9}") (class "Default")
      (node (ref "E25") (pin "5") (pinfunction "Y3_5") (pintype "input"))
      (node (ref "E29") (pin "4") (pinfunction "O_4") (pintype "open_collector"))
      (node (ref "U$2") (pin "DS1") (pinfunction "1_DS1") (pintype "bidirectional"))
    )
    (net (code "163") (name "~{DATA10}") (class "Default")
      (node (ref "E25") (pin "3") (pinfunction "Y2_3") (pintype "input"))
      (node (ref "E29") (pin "10") (pinfunction "O_10") (pintype "open_collector"))
      (node (ref "U$2") (pin "DU1") (pinfunction "1_DU1") (pintype "bidirectional"))
    )
    (net (code "164") (name "~{DATA11}") (class "Default")
      (node (ref "E25") (pin "1") (pinfunction "Y1_1") (pintype "input"))
      (node (ref "E29") (pin "13") (pinfunction "O_13") (pintype "open_collector"))
      (node (ref "U$2") (pin "DV1") (pinfunction "1_DV1") (pintype "bidirectional"))
    )
    (net (code "165") (name "~{DONE_SKIP}") (class "Default")
      (node (ref "E10") (pin "11") (pinfunction "I2_11") (pintype "input"))
      (node (ref "E19") (pin "9") (pinfunction "I1_9") (pintype "input"))
      (node (ref "E34") (pin "11") (pinfunction "O_11") (pintype "output"))
      (node (ref "U$2") (pin "CB1") (pinfunction "1_CB1") (pintype "bidirectional"))
    )
    (net (code "166") (name "~{DONE}") (class "Default")
      (node (ref "E10") (pin "4") (pinfunction "I1_4") (pintype "input"))
      (node (ref "E28") (pin "10") (pinfunction "I1_10") (pintype "input"))
      (node (ref "E32") (pin "8") (pinfunction "O_8") (pintype "output"))
    )
    (net (code "167") (name "~{ENB_BUF_LD}") (class "Default")
      (node (ref "E16") (pin "11") (pinfunction "O_11") (pintype "output"))
      (node (ref "E20") (pin "13") (pinfunction "I2_13") (pintype "input"))
      (node (ref "E21") (pin "13") (pinfunction "SHF_13") (pintype "input"))
      (node (ref "E33") (pin "13") (pinfunction "SHF_13") (pintype "input"))
      (node (ref "E4") (pin "9") (pinfunction "LD_9") (pintype "input"))
      (node (ref "E9") (pin "13") (pinfunction "SHF_13") (pintype "input"))
    )
    (net (code "168") (name "~{ERR_SKIP}") (class "Default")
      (node (ref "E10") (pin "10") (pinfunction "I1_10") (pintype "input"))
      (node (ref "E23") (pin "9") (pinfunction "I1_9") (pintype "input"))
      (node (ref "E34") (pin "3") (pinfunction "O_3") (pintype "output"))
    )
    (net (code "169") (name "~{INIT_IOT}") (class "Default")
      (node (ref "E41") (pin "9") (pinfunction "O7_9") (pintype "output"))
      (node (ref "E7") (pin "2") (pinfunction "D_2") (pintype "input"))
    )
    (net (code "170") (name "~{INIT}") (class "Default")
      (node (ref "E16") (pin "10") (pinfunction "I1_10") (pintype "input"))
      (node (ref "E2") (pin "1") (pinfunction "CLR_1") (pintype "input"))
      (node (ref "E2") (pin "13") (pinfunction "CLR_13") (pintype "input"))
      (node (ref "E21") (pin "1") (pinfunction "CLR_1") (pintype "input"))
      (node (ref "E33") (pin "1") (pinfunction "CLR_1") (pintype "input"))
      (node (ref "E4") (pin "1") (pinfunction "CLR_1") (pintype "input"))
      (node (ref "E8") (pin "6") (pinfunction "O_6") (pintype "output"))
      (node (ref "E9") (pin "1") (pinfunction "CLR_1") (pintype "input"))
    )
    (net (code "171") (name "~{INTERNAL_IO}") (class "Default")
      (node (ref "E18") (pin "1") (pinfunction "O_1") (pintype "open_collector"))
      (node (ref "U$2") (pin "CL1") (pinfunction "1_CL1") (pintype "bidirectional"))
    )
    (net (code "172") (name "~{INTR_IOT}") (class "Default")
      (node (ref "E41") (pin "7") (pinfunction "O6_7") (pintype "output"))
      (node (ref "E6") (pin "6") (pinfunction "I1_6") (pintype "input"))
    )
    (net (code "173") (name "~{INT_RQST}") (class "Default")
      (node (ref "E18") (pin "4") (pinfunction "O_4") (pintype "open_collector"))
      (node (ref "U$2") (pin "CP1") (pinfunction "1_CP1") (pintype "bidirectional"))
    )
    (net (code "174") (name "~{IO_PAUSE}") (class "Default")
      (node (ref "E39") (pin "6") (pinfunction "I0_6") (pintype "input"))
      (node (ref "U$2") (pin "CD1") (pinfunction "1_CD1") (pintype "bidirectional"))
    )
    (net (code "175") (name "~{LCD_IOT}") (class "Default")
      (node (ref "E12") (pin "4") (pinfunction "I0_4") (pintype "input"))
      (node (ref "E16") (pin "5") (pinfunction "I1_5") (pintype "input"))
      (node (ref "E38") (pin "3") (pinfunction "I_3") (pintype "input"))
      (node (ref "E41") (pin "2") (pinfunction "O1_2") (pintype "output"))
      (node (ref "E6") (pin "3") (pinfunction "I1_3") (pintype "input"))
    )
    (net (code "176") (name "~{MAINT}") (class "Default")
      (node (ref "E10") (pin "3") (pinfunction "I0_3") (pintype "input"))
      (node (ref "E16") (pin "12") (pinfunction "I0_12") (pintype "input"))
      (node (ref "E2") (pin "8") (pinfunction "~{Q}_8") (pintype "output"))
      (node (ref "E22") (pin "4") (pinfunction "PRE_4") (pintype "input"))
      (node (ref "E26") (pin "4") (pinfunction "PRE_4") (pintype "input"))
      (node (ref "E28") (pin "1") (pinfunction "I0_1") (pintype "input"))
      (node (ref "E28") (pin "12") (pinfunction "I2_12") (pintype "input"))
      (node (ref "E30") (pin "4") (pinfunction "PRE_4") (pintype "input"))
      (node (ref "E32") (pin "11") (pinfunction "I_11") (pintype "input"))
    )
    (net (code "177") (name "~{MD03}") (class "Default")
      (node (ref "E35") (pin "4") (pinfunction "I0_4") (pintype "input"))
      (node (ref "U$2") (pin "AP1") (pinfunction "1_AP1") (pintype "bidirectional"))
    )
    (net (code "178") (name "~{MD04}") (class "Default")
      (node (ref "E35") (pin "6") (pinfunction "I2_6") (pintype "input"))
      (node (ref "U$2") (pin "BK1") (pinfunction "1_BK1") (pintype "bidirectional"))
    )
    (net (code "179") (name "~{MD05}") (class "Default")
      (node (ref "E35") (pin "5") (pinfunction "I1_5") (pintype "input"))
      (node (ref "U$2") (pin "BL1") (pinfunction "1_BL1") (pintype "bidirectional"))
    )
    (net (code "180") (name "~{MD06}") (class "Default")
      (node (ref "E31") (pin "4") (pinfunction "4_4") (pintype "passive"))
      (node (ref "E40") (pin "1") (pinfunction "Y1_1") (pintype "input"))
      (node (ref "U$2") (pin "BM1") (pinfunction "1_BM1") (pintype "bidirectional"))
    )
    (net (code "181") (name "~{MD07}") (class "Default")
      (node (ref "E31") (pin "5") (pinfunction "5_5") (pintype "passive"))
      (node (ref "E40") (pin "3") (pinfunction "Y2_3") (pintype "input"))
      (node (ref "U$2") (pin "BP1") (pinfunction "1_BP1") (pintype "bidirectional"))
    )
    (net (code "182") (name "~{MD08}") (class "Default")
      (node (ref "E31") (pin "6") (pinfunction "6_6") (pintype "passive"))
      (node (ref "E40") (pin "5") (pinfunction "Y3_5") (pintype "input"))
      (node (ref "U$2") (pin "DK1") (pinfunction "1_DK1") (pintype "bidirectional"))
    )
    (net (code "183") (name "~{MD09}") (class "Default")
      (node (ref "E40") (pin "15") (pinfunction "Y3_15") (pintype "input"))
      (node (ref "U$2") (pin "DL1") (pinfunction "1_DL1") (pintype "bidirectional"))
    )
    (net (code "184") (name "~{MD10}") (class "Default")
      (node (ref "E40") (pin "13") (pinfunction "Y2_13") (pintype "input"))
      (node (ref "U$2") (pin "DM1") (pinfunction "1_DM1") (pintype "bidirectional"))
    )
    (net (code "185") (name "~{MD11}") (class "Default")
      (node (ref "E40") (pin "11") (pinfunction "Y1_11") (pintype "input"))
      (node (ref "U$2") (pin "DP1") (pinfunction "1_DP1") (pintype "bidirectional"))
    )
    (net (code "186") (name "~{PARITY}") (class "Default")
      (node (ref "E24") (pin "12") (pinfunction "I0_12") (pintype "input"))
      (node (ref "E27") (pin "14") (pinfunction "~{Q}_14") (pintype "output"))
    )
    (net (code "187") (name "~{RX8_SEL}") (class "Default")
      (node (ref "E1") (pin "7") (pinfunction "FORCE0_7") (pintype "input"))
      (node (ref "E1") (pin "9") (pinfunction "FORCE0_9") (pintype "input"))
      (node (ref "E25") (pin "7") (pinfunction "FORCE0_7") (pintype "input"))
      (node (ref "E25") (pin "9") (pinfunction "FORCE0_9") (pintype "input"))
      (node (ref "E32") (pin "6") (pinfunction "O_6") (pintype "output"))
    )
    (net (code "188") (name "~{RX_12_BIT}") (class "Default")
      (node (ref "DRIVE") (pin "FF") (pinfunction "28_FF") (pintype "bidirectional"))
      (node (ref "E14") (pin "10") (pinfunction "O_10") (pintype "open_collector"))
      (node (ref "R16") (pin "2") (pinfunction "2_2") (pintype "passive"))
      (node (ref "R7") (pin "1") (pinfunction "1_1") (pintype "passive"))
    )
    (net (code "189") (name "~{RX_DATA}") (class "Default")
      (node (ref "DRIVE") (pin "BB") (pinfunction "24_BB") (pintype "bidirectional"))
      (node (ref "E14") (pin "4") (pinfunction "O_4") (pintype "open_collector"))
      (node (ref "E36") (pin "11") (pinfunction "Y1_11") (pintype "input"))
      (node (ref "R17") (pin "2") (pinfunction "2_2") (pintype "passive"))
      (node (ref "R8") (pin "1") (pinfunction "1_1") (pintype "passive"))
    )
    (net (code "190") (name "~{RX_DONE}") (class "Default")
      (node (ref "DRIVE") (pin "X") (pinfunction "20_X") (pintype "bidirectional"))
      (node (ref "E36") (pin "5") (pinfunction "Y3_5") (pintype "input"))
      (node (ref "R13") (pin "2") (pinfunction "2_2") (pintype "passive"))
      (node (ref "R4") (pin "1") (pinfunction "1_1") (pintype "passive"))
    )
    (net (code "191") (name "~{RX_ERROR}") (class "Default")
      (node (ref "DRIVE") (pin "J") (pinfunction "8_J") (pintype "bidirectional"))
      (node (ref "E36") (pin "1") (pinfunction "Y1_1") (pintype "input"))
      (node (ref "R14") (pin "2") (pinfunction "2_2") (pintype "passive"))
      (node (ref "R5") (pin "1") (pinfunction "1_1") (pintype "passive"))
    )
    (net (code "192") (name "~{RX_INIT}") (class "Default")
      (node (ref "DRIVE") (pin "N") (pinfunction "12_N") (pintype "bidirectional"))
      (node (ref "E37") (pin "13") (pinfunction "O_13") (pintype "open_collector"))
      (node (ref "R9") (pin "1") (pinfunction "1_1") (pintype "passive"))
    )
    (net (code "193") (name "~{RX_OUT}") (class "Default")
      (node (ref "DRIVE") (pin "RR") (pinfunction "36_RR") (pintype "bidirectional"))
      (node (ref "E36") (pin "15") (pinfunction "Y3_15") (pintype "input"))
      (node (ref "R12") (pin "2") (pinfunction "2_2") (pintype "passive"))
      (node (ref "R3") (pin "1") (pinfunction "1_1") (pintype "passive"))
    )
    (net (code "194") (name "~{RX_RUN}") (class "Default")
      (node (ref "DRIVE") (pin "D") (pinfunction "4_D") (pintype "bidirectional"))
      (node (ref "E18") (pin "13") (pinfunction "O_13") (pintype "open_collector"))
      (node (ref "R15") (pin "2") (pinfunction "2_2") (pintype "passive"))
      (node (ref "R6") (pin "1") (pinfunction "1_1") (pintype "passive"))
    )
    (net (code "195") (name "~{RX_SHIFT}") (class "Default")
      (node (ref "DRIVE") (pin "LL") (pinfunction "32_LL") (pintype "bidirectional"))
      (node (ref "E36") (pin "13") (pinfunction "Y2_13") (pintype "input"))
      (node (ref "R10") (pin "2") (pinfunction "2_2") (pintype "passive"))
      (node (ref "R2") (pin "1") (pinfunction "1_1") (pintype "passive"))
    )
    (net (code "196") (name "~{RX_TR_REQ}") (class "Default")
      (node (ref "DRIVE") (pin "T") (pinfunction "16_T") (pintype "bidirectional"))
      (node (ref "E36") (pin "3") (pinfunction "Y2_3") (pintype "input"))
      (node (ref "R1") (pin "1") (pinfunction "1_1") (pintype "passive"))
      (node (ref "R11") (pin "2") (pinfunction "2_2") (pintype "passive"))
    )
    (net (code "197") (name "~{SDN_IOT}") (class "Default")
      (node (ref "E38") (pin "11") (pinfunction "I_11") (pintype "input"))
      (node (ref "E41") (pin "6") (pinfunction "O5_6") (pintype "output"))
    )
    (net (code "198") (name "~{SER_IOT}") (class "Default")
      (node (ref "E38") (pin "9") (pinfunction "I_9") (pintype "input"))
      (node (ref "E41") (pin "5") (pinfunction "O4_5") (pintype "output"))
    )
    (net (code "199") (name "~{SKIP}") (class "Default")
      (node (ref "E18") (pin "10") (pinfunction "O_10") (pintype "open_collector"))
      (node (ref "U$2") (pin "CS1") (pinfunction "1_CS1") (pintype "bidirectional"))
    )
    (net (code "200") (name "~{STR_IOT}") (class "Default")
      (node (ref "E38") (pin "13") (pinfunction "I_13") (pintype "input"))
      (node (ref "E41") (pin "4") (pinfunction "O3_4") (pintype "output"))
    )
    (net (code "201") (name "~{TP3}") (class "Default")
      (node (ref "E11") (pin "14") (pinfunction "O_14") (pintype "output"))
      (node (ref "E19") (pin "8") (pinfunction "I0_8") (pintype "input"))
      (node (ref "E20") (pin "1") (pinfunction "I0_1") (pintype "input"))
      (node (ref "E23") (pin "11") (pinfunction "I0_11") (pintype "input"))
      (node (ref "E23") (pin "8") (pinfunction "I0_8") (pintype "input"))
      (node (ref "E32") (pin "13") (pinfunction "I_13") (pintype "input"))
      (node (ref "E6") (pin "2") (pinfunction "I0_2") (pintype "input"))
      (node (ref "E6") (pin "5") (pinfunction "I0_5") (pintype "input"))
    )
    (net (code "202") (name "~{TR_SKIP}") (class "Default")
      (node (ref "E10") (pin "9") (pinfunction "I0_9") (pintype "input"))
      (node (ref "E23") (pin "12") (pinfunction "I1_12") (pintype "input"))
      (node (ref "E34") (pin "8") (pinfunction "O_8") (pintype "output"))
      (node (ref "U$2") (pin "DB1") (pinfunction "1_DB1") (pintype "bidirectional"))
    )
    (net (code "203") (name "~{XFER_IOT}") (class "Default")
      (node (ref "E16") (pin "4") (pinfunction "I0_4") (pintype "input"))
      (node (ref "E19") (pin "12") (pinfunction "I1_12") (pintype "input"))
      (node (ref "E38") (pin "5") (pinfunction "I_5") (pintype "input"))
      (node (ref "E41") (pin "3") (pinfunction "O2_3") (pintype "output"))
    )
  )
)
